# io-board-f-a.net
KiCad netlist of a schematic drawn in EAGLE
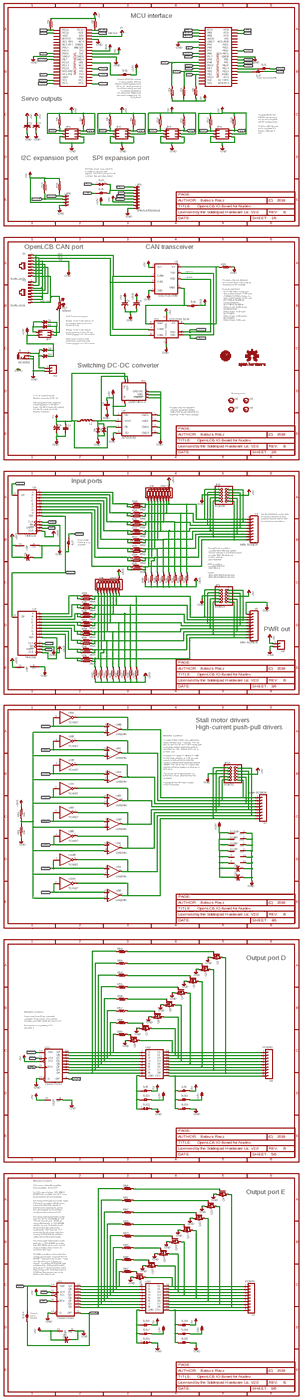
[diagram p0: schematic, sheet 1, overview]
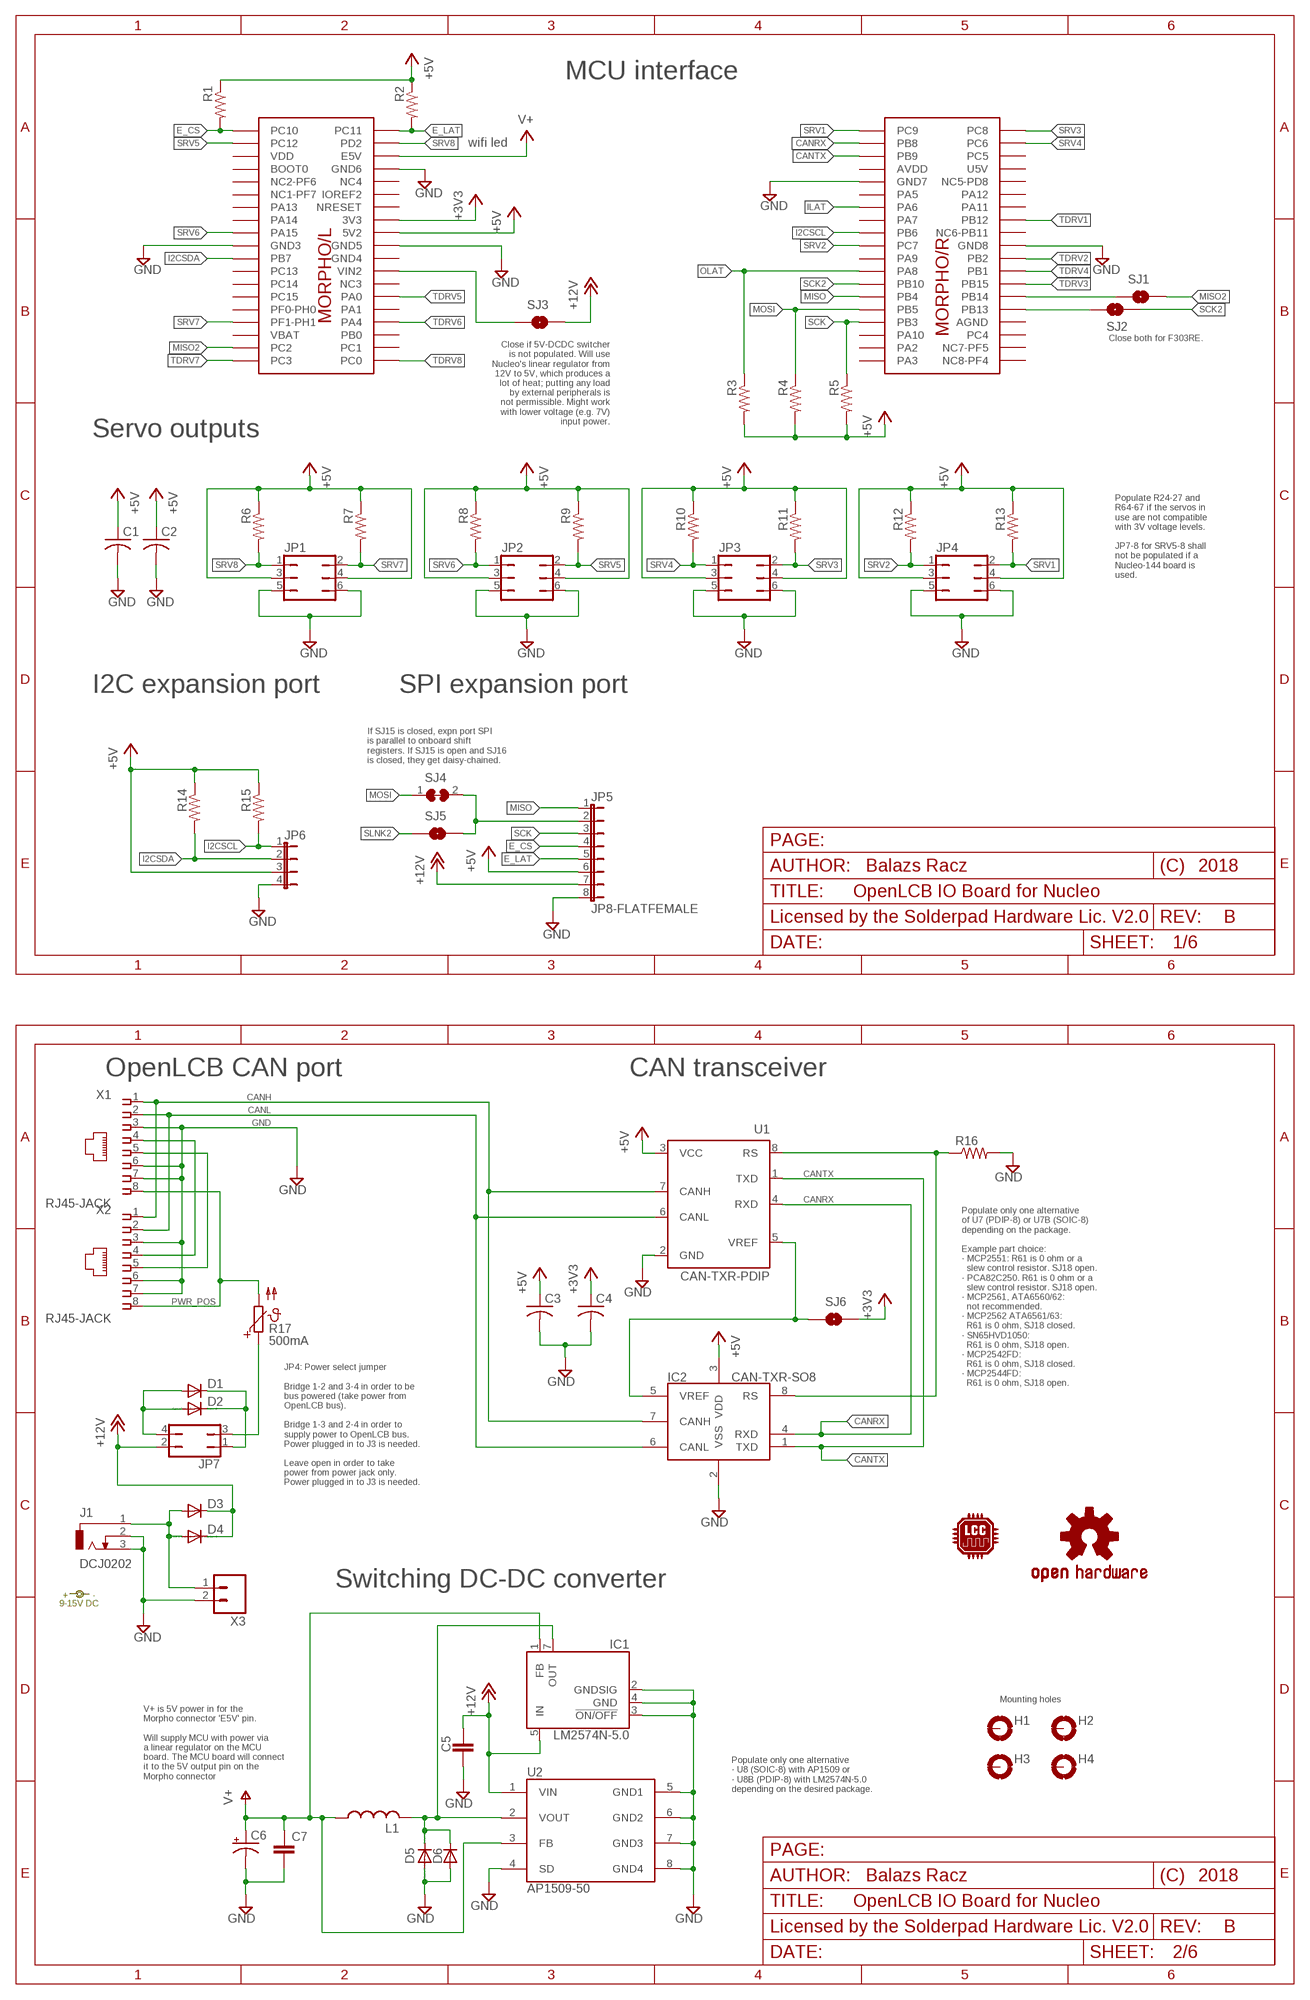
[diagram p1: schematic, sheet 1, part 1 of 4]
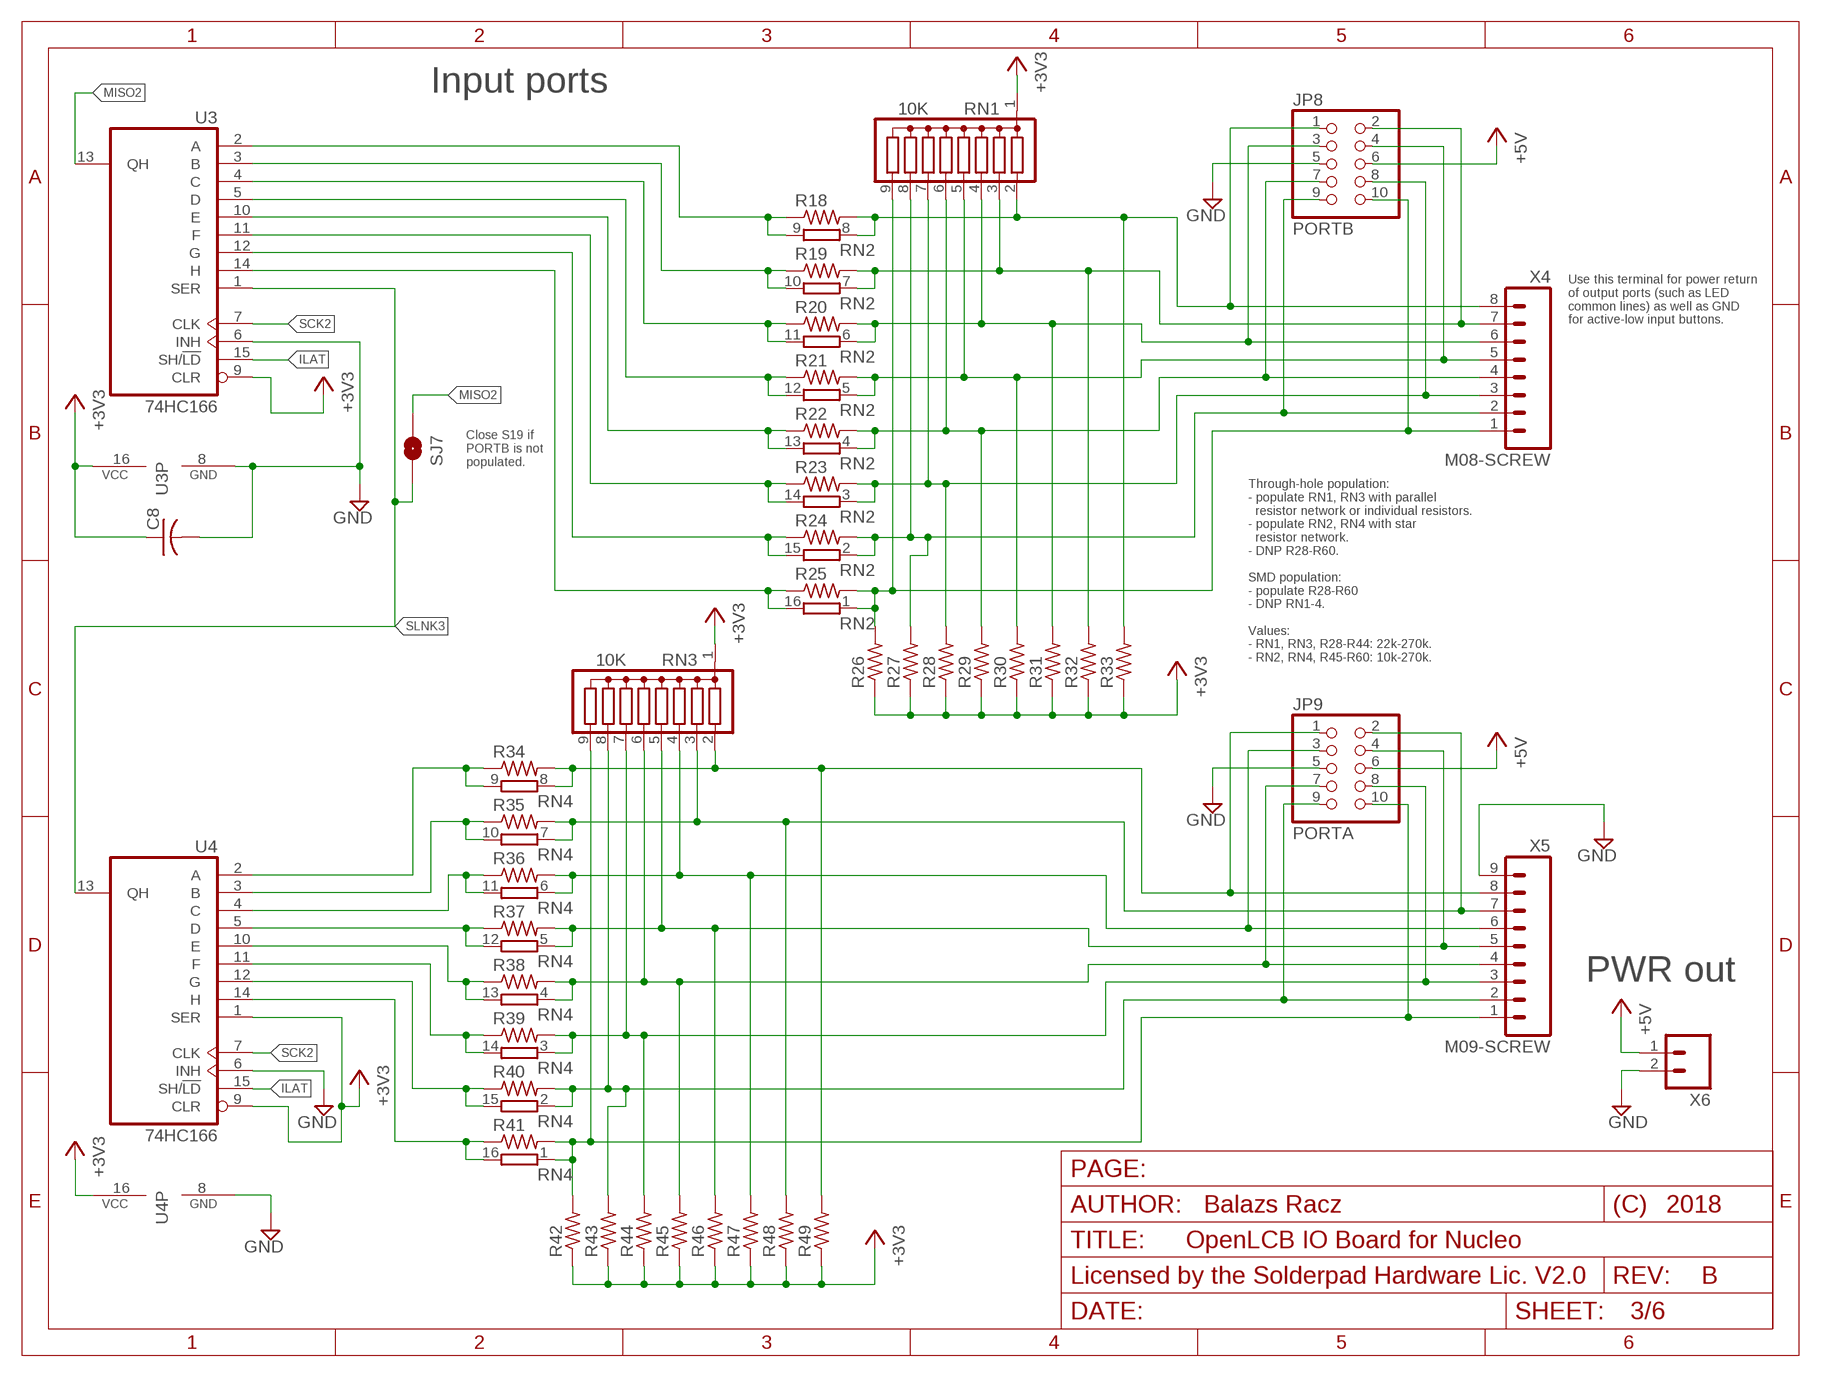
[diagram p2: schematic, sheet 1, part 2 of 4]
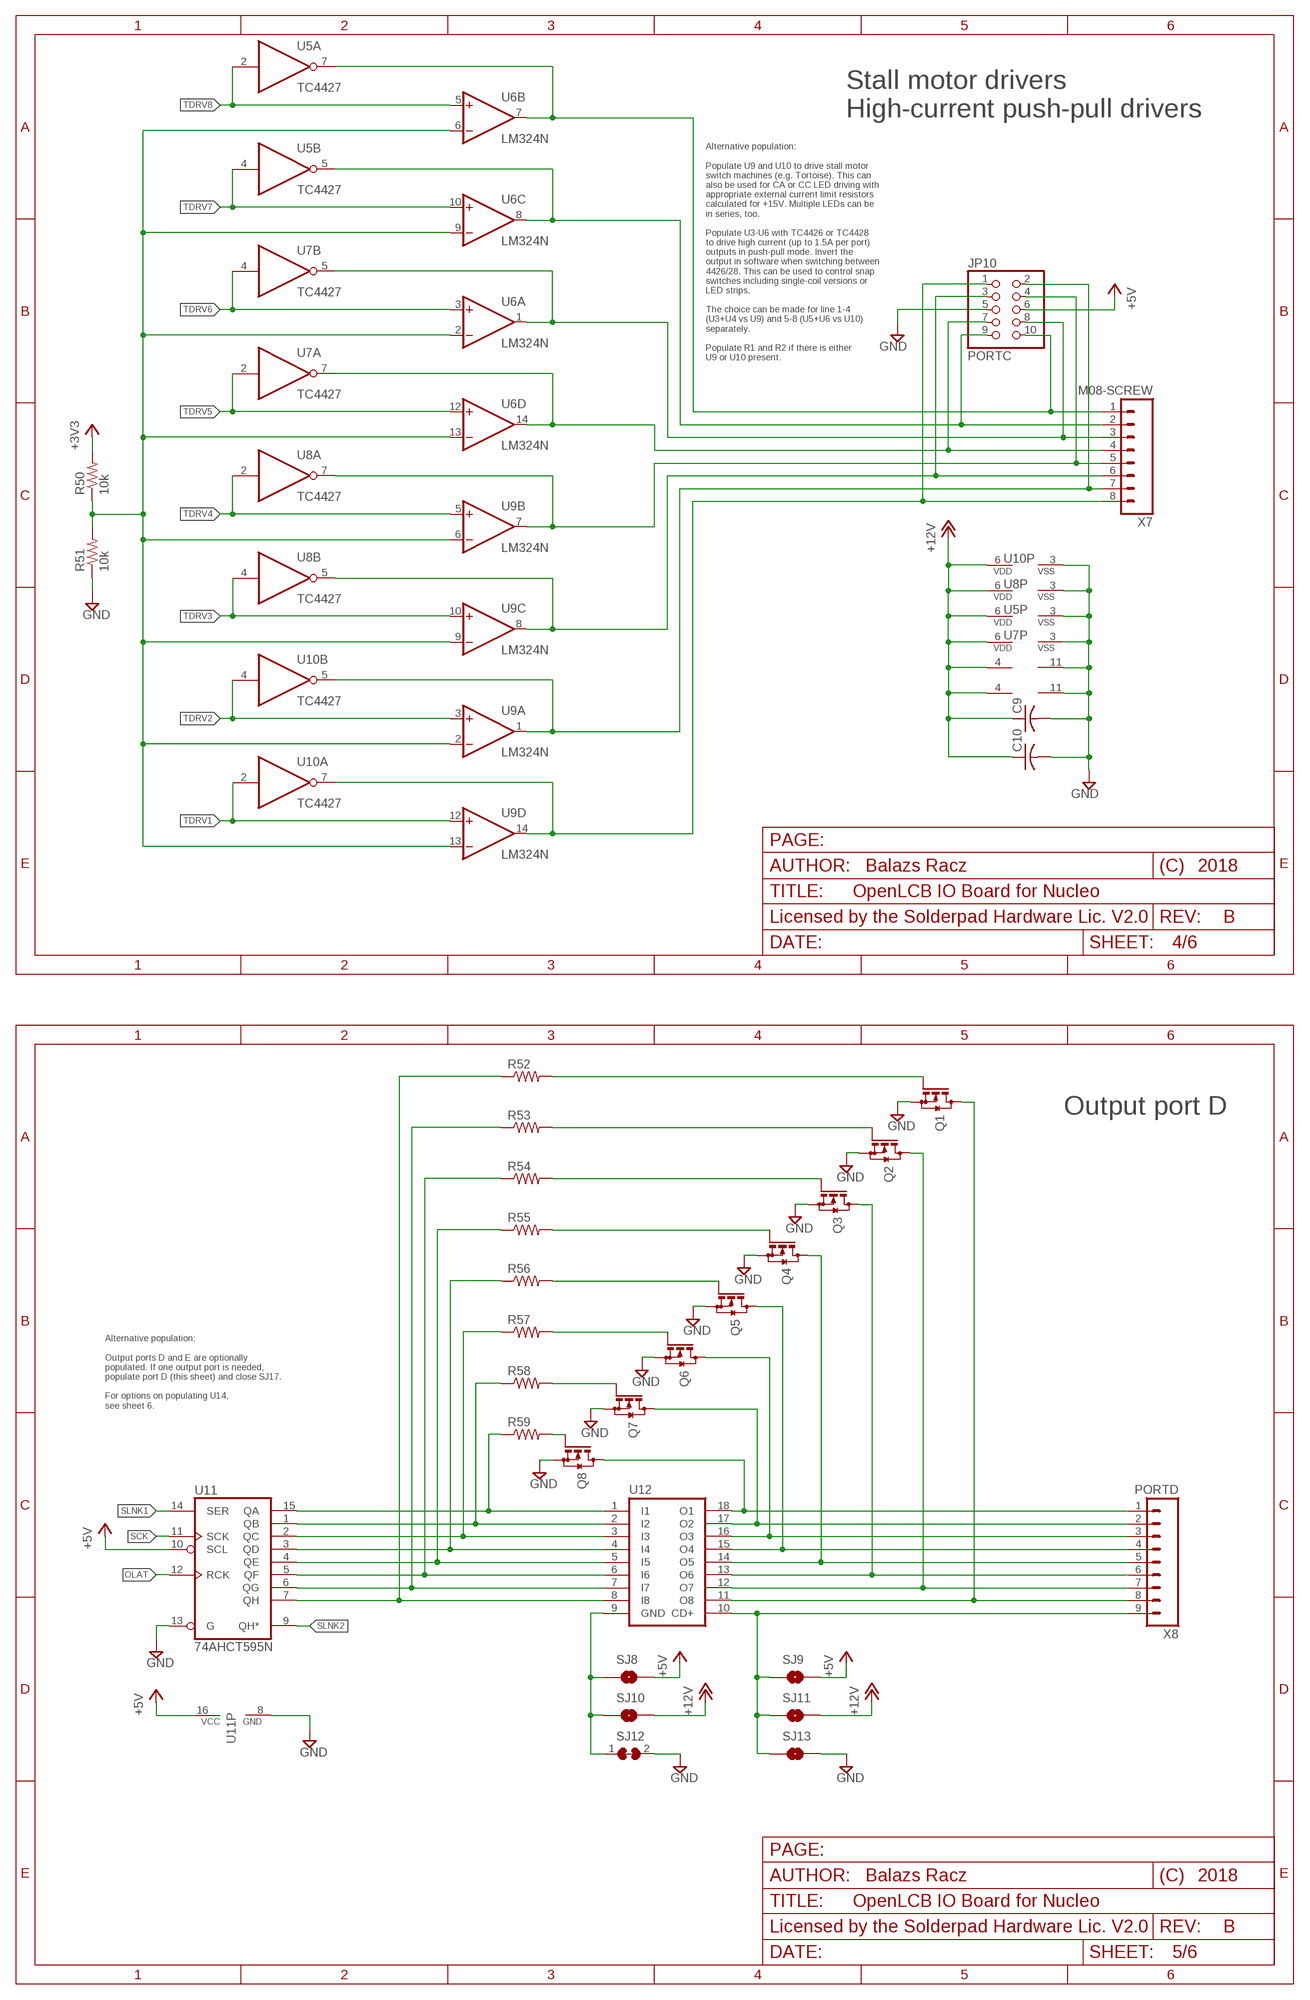
[diagram p3: schematic, sheet 1, part 3 of 4]
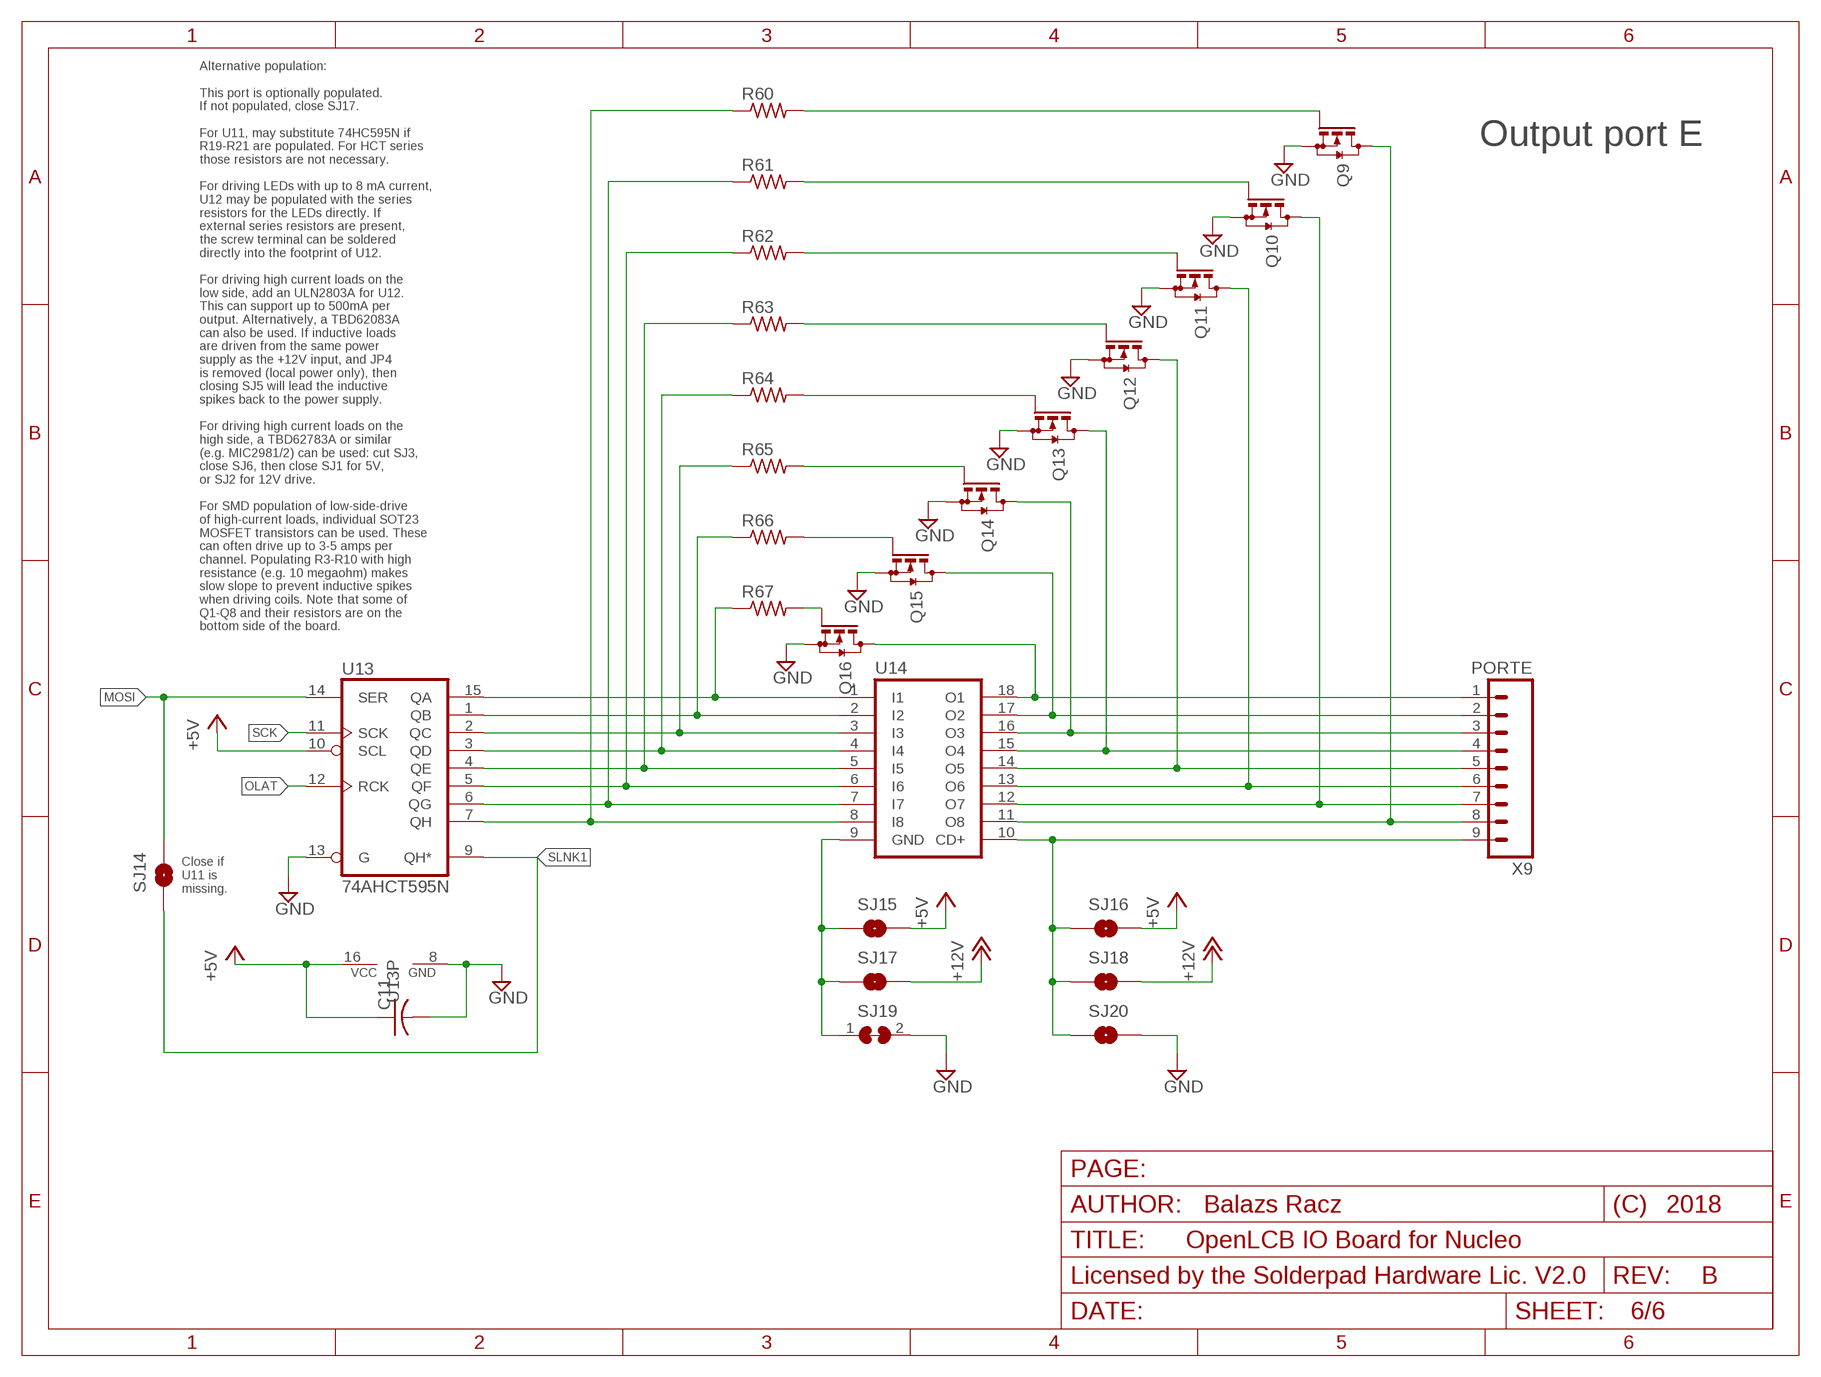
[diagram p4: schematic, sheet 1, part 4 of 4]

(export (version "E")
  (design (tool "Eeschema 10.0.6"))
  (components
    (comp (ref "C1")
      (value "C-USC1206")
      (footprint "eagle-import:C1206")
      (libsource (lib "eagle-import") (part "C-USC1206"))
    )
    (comp (ref "C2")
      (value "C-USC1206")
      (footprint "eagle-import:C1206")
      (libsource (lib "eagle-import") (part "C-USC1206"))
    )
    (comp (ref "C3")
      (value "C-USC0805")
      (footprint "eagle-import:C0805")
      (libsource (lib "eagle-import") (part "C-USC0805"))
    )
    (comp (ref "C4")
      (value "C-USC0805")
      (footprint "eagle-import:C0805")
      (libsource (lib "eagle-import") (part "C-USC0805"))
    )
    (comp (ref "C5")
      (value "C-EUC1206")
      (footprint "eagle-import:C1206")
      (libsource (lib "eagle-import") (part "C-EUC1206"))
    )
    (comp (ref "C6")
      (value "CPOL-USE2.5-5")
      (footprint "eagle-import:E2,5-5")
      (libsource (lib "eagle-import") (part "CPOL-USE2.5-5"))
    )
    (comp (ref "C7")
      (value "C-EUC1206")
      (footprint "eagle-import:C1206")
      (libsource (lib "eagle-import") (part "C-EUC1206"))
    )
    (comp (ref "C8")
      (value "C-USC0805")
      (footprint "eagle-import:C0805")
      (libsource (lib "eagle-import") (part "C-USC0805"))
    )
    (comp (ref "C9")
      (value "C-USC1206")
      (footprint "eagle-import:C1206")
      (libsource (lib "eagle-import") (part "C-USC1206"))
    )
    (comp (ref "C10")
      (value "C-USC1206")
      (footprint "eagle-import:C1206")
      (libsource (lib "eagle-import") (part "C-USC1206"))
    )
    (comp (ref "C11")
      (value "C-USC0805")
      (footprint "eagle-import:C0805")
      (libsource (lib "eagle-import") (part "C-USC0805"))
    )
    (comp (ref "D1")
      (value "DIODEDO-214AA-NODOC")
      (footprint "eagle-import:DO214AA-NODOC")
      (libsource (lib "eagle-import") (part "DIODEDO-214AA-NODOC"))
    )
    (comp (ref "D2")
      (value "DIODE-DO41-7.6")
      (footprint "eagle-import:DO41-7.6")
      (libsource (lib "eagle-import") (part "DIODE-DO41-7.6"))
    )
    (comp (ref "D3")
      (value "DIODEDO-214AA-NODOC")
      (footprint "eagle-import:DO214AA-NODOC")
      (libsource (lib "eagle-import") (part "DIODEDO-214AA-NODOC"))
    )
    (comp (ref "D4")
      (value "DIODE-DO41-7.6")
      (footprint "eagle-import:DO41-7.6")
      (libsource (lib "eagle-import") (part "DIODE-DO41-7.6"))
    )
    (comp (ref "D5")
      (value "DIODE-DO41-7.6")
      (footprint "eagle-import:DO41-7.6")
      (libsource (lib "eagle-import") (part "DIODE-DO41-7.6"))
    )
    (comp (ref "D6")
      (value "DIODEDO-214AA-NODOC")
      (footprint "eagle-import:DO214AA-NODOC")
      (libsource (lib "eagle-import") (part "DIODEDO-214AA-NODOC"))
    )
    (comp (ref "G1")
      (value "NUCLEO_64_GENERIC")
      (footprint "eagle-import:NUCLEO_BRD_BASE64")
      (libsource (lib "eagle-import") (part "NUCLEO_64_GENERIC"))
    )
    (comp (ref "H1")
      (value "MOUNT-PAD-ROUND3.3")
      (footprint "eagle-import:3,3-PAD")
      (libsource (lib "eagle-import") (part "MOUNT-PAD-ROUND3.3"))
    )
    (comp (ref "H2")
      (value "MOUNT-PAD-ROUND3.3")
      (footprint "eagle-import:3,3-PAD")
      (libsource (lib "eagle-import") (part "MOUNT-PAD-ROUND3.3"))
    )
    (comp (ref "H3")
      (value "MOUNT-PAD-ROUND3.3")
      (footprint "eagle-import:3,3-PAD")
      (libsource (lib "eagle-import") (part "MOUNT-PAD-ROUND3.3"))
    )
    (comp (ref "H4")
      (value "MOUNT-PAD-ROUND3.3")
      (footprint "eagle-import:3,3-PAD")
      (libsource (lib "eagle-import") (part "MOUNT-PAD-ROUND3.3"))
    )
    (comp (ref "IC1")
      (value "LM2574N-5.0")
      (footprint "eagle-import:DIL08")
      (libsource (lib "eagle-import") (part "LM2574?-N5.0"))
    )
    (comp (ref "IC2")
      (value "CAN-TXR-SO8")
      (footprint "eagle-import:SO-08")
      (libsource (lib "eagle-import") (part "MCP2551-SN"))
    )
    (comp (ref "J1")
      (value "DCJ0202")
      (footprint "eagle-import:DCJ0202")
      (libsource (lib "eagle-import") (part "DCJ0202"))
    )
    (comp (ref "JP1")
      (value "JP3Q")
      (footprint "eagle-import:JP3Q")
      (libsource (lib "eagle-import") (part "JP3Q"))
    )
    (comp (ref "JP2")
      (value "JP3Q")
      (footprint "eagle-import:JP3Q")
      (libsource (lib "eagle-import") (part "JP3Q"))
    )
    (comp (ref "JP3")
      (value "JP3Q")
      (footprint "eagle-import:JP3Q")
      (libsource (lib "eagle-import") (part "JP3Q"))
    )
    (comp (ref "JP4")
      (value "JP3Q")
      (footprint "eagle-import:JP3Q")
      (libsource (lib "eagle-import") (part "JP3Q"))
    )
    (comp (ref "JP5")
      (value "JP8-FLATFEMALE")
      (footprint "eagle-import:JP8F-FEM")
      (libsource (lib "eagle-import") (part "JP8-FLATFEMALE"))
    )
    (comp (ref "JP6")
      (value "JP4-FLAT")
      (footprint "eagle-import:JP4F")
      (libsource (lib "eagle-import") (part "JP4-FLAT"))
    )
    (comp (ref "JP7")
      (value "JP2Q")
      (footprint "eagle-import:JP2Q")
      (libsource (lib "eagle-import") (part "JP2Q"))
    )
    (comp (ref "JP8")
      (value "PORTB")
      (footprint "eagle-import:CON10M")
      (libsource (lib "eagle-import") (part "PINHD-2X5CN"))
    )
    (comp (ref "JP9")
      (value "PORTA")
      (footprint "eagle-import:CON10M")
      (libsource (lib "eagle-import") (part "PINHD-2X5CN"))
    )
    (comp (ref "JP10")
      (value "PORTC")
      (footprint "eagle-import:CON10M")
      (libsource (lib "eagle-import") (part "PINHD-2X5CN"))
    )
    (comp (ref "L1")
      (value "L-US")
      (footprint "eagle-import:L5-8,5")
      (libsource (lib "eagle-import") (part "L-US"))
    )
    (comp (ref "LG1")
      (value "LCC_LOGO")
      (footprint "eagle-import:LCC_LOGO")
      (libsource (lib "eagle-import") (part "LCC_LOGO"))
    )
    (comp (ref "LOGO1")
      (value "DOC-OSHW-LOGOM")
      (footprint "eagle-import:OSHW-LOGO-M")
      (libsource (lib "eagle-import") (part "DOC-OSHW-LOGOM"))
    )
    (comp (ref "P1")
      (value "9-15V DC")
      (footprint "eagle-import:POWER_USAGE")
      (libsource (lib "eagle-import") (part "DOC-POWER_LABEL"))
    )
    (comp (ref "Q1")
      (value "BSS123")
      (footprint "eagle-import:SOT23")
      (libsource (lib "eagle-import") (part "BSS123"))
    )
    (comp (ref "Q2")
      (value "BSS123")
      (footprint "eagle-import:SOT23")
      (libsource (lib "eagle-import") (part "BSS123"))
    )
    (comp (ref "Q3")
      (value "BSS123")
      (footprint "eagle-import:SOT23")
      (libsource (lib "eagle-import") (part "BSS123"))
    )
    (comp (ref "Q4")
      (value "BSS123")
      (footprint "eagle-import:SOT23")
      (libsource (lib "eagle-import") (part "BSS123"))
    )
    (comp (ref "Q5")
      (value "BSS123")
      (footprint "eagle-import:SOT23")
      (libsource (lib "eagle-import") (part "BSS123"))
    )
    (comp (ref "Q6")
      (value "BSS123")
      (footprint "eagle-import:SOT23")
      (libsource (lib "eagle-import") (part "BSS123"))
    )
    (comp (ref "Q7")
      (value "BSS123")
      (footprint "eagle-import:SOT23")
      (libsource (lib "eagle-import") (part "BSS123"))
    )
    (comp (ref "Q8")
      (value "BSS123")
      (footprint "eagle-import:SOT23")
      (libsource (lib "eagle-import") (part "BSS123"))
    )
    (comp (ref "Q9")
      (value "BSS123")
      (footprint "eagle-import:SOT23")
      (libsource (lib "eagle-import") (part "BSS123"))
    )
    (comp (ref "Q10")
      (value "BSS123")
      (footprint "eagle-import:SOT23")
      (libsource (lib "eagle-import") (part "BSS123"))
    )
    (comp (ref "Q11")
      (value "BSS123")
      (footprint "eagle-import:SOT23")
      (libsource (lib "eagle-import") (part "BSS123"))
    )
    (comp (ref "Q12")
      (value "BSS123")
      (footprint "eagle-import:SOT23")
      (libsource (lib "eagle-import") (part "BSS123"))
    )
    (comp (ref "Q13")
      (value "BSS123")
      (footprint "eagle-import:SOT23")
      (libsource (lib "eagle-import") (part "BSS123"))
    )
    (comp (ref "Q14")
      (value "BSS123")
      (footprint "eagle-import:SOT23")
      (libsource (lib "eagle-import") (part "BSS123"))
    )
    (comp (ref "Q15")
      (value "BSS123")
      (footprint "eagle-import:SOT23")
      (libsource (lib "eagle-import") (part "BSS123"))
    )
    (comp (ref "Q16")
      (value "BSS123")
      (footprint "eagle-import:SOT23")
      (libsource (lib "eagle-import") (part "BSS123"))
    )
    (comp (ref "R1")
      (value "R-US_R0805")
      (footprint "eagle-import:R0805")
      (libsource (lib "eagle-import") (part "rcl_334_R-US_R0805"))
    )
    (comp (ref "R2")
      (value "R-US_R0805")
      (footprint "eagle-import:R0805")
      (libsource (lib "eagle-import") (part "rcl_334_R-US_R0805"))
    )
    (comp (ref "R3")
      (value "R-US_R0805")
      (footprint "eagle-import:R0805")
      (libsource (lib "eagle-import") (part "rcl_334_R-US_R0805"))
    )
    (comp (ref "R4")
      (value "R-US_R0805")
      (footprint "eagle-import:R0805")
      (libsource (lib "eagle-import") (part "rcl_334_R-US_R0805"))
    )
    (comp (ref "R5")
      (value "R-US_R0805")
      (footprint "eagle-import:R0805")
      (libsource (lib "eagle-import") (part "rcl_334_R-US_R0805"))
    )
    (comp (ref "R6")
      (value "R-US_R0805")
      (footprint "eagle-import:R0805")
      (libsource (lib "eagle-import") (part "rcl_334_R-US_R0805"))
    )
    (comp (ref "R7")
      (value "R-US_R0805")
      (footprint "eagle-import:R0805")
      (libsource (lib "eagle-import") (part "rcl_334_R-US_R0805"))
    )
    (comp (ref "R8")
      (value "R-US_R0805")
      (footprint "eagle-import:R0805")
      (libsource (lib "eagle-import") (part "rcl_334_R-US_R0805"))
    )
    (comp (ref "R9")
      (value "R-US_R0805")
      (footprint "eagle-import:R0805")
      (libsource (lib "eagle-import") (part "rcl_334_R-US_R0805"))
    )
    (comp (ref "R10")
      (value "R-US_R0805")
      (footprint "eagle-import:R0805")
      (libsource (lib "eagle-import") (part "rcl_334_R-US_R0805"))
    )
    (comp (ref "R11")
      (value "R-US_R0805")
      (footprint "eagle-import:R0805")
      (libsource (lib "eagle-import") (part "rcl_334_R-US_R0805"))
    )
    (comp (ref "R12")
      (value "R-US_R0805")
      (footprint "eagle-import:R0805")
      (libsource (lib "eagle-import") (part "rcl_334_R-US_R0805"))
    )
    (comp (ref "R13")
      (value "R-US_R0805")
      (footprint "eagle-import:R0805")
      (libsource (lib "eagle-import") (part "rcl_334_R-US_R0805"))
    )
    (comp (ref "R14")
      (value "R-US_R0805")
      (footprint "eagle-import:R0805")
      (libsource (lib "eagle-import") (part "rcl_334_R-US_R0805"))
    )
    (comp (ref "R15")
      (value "R-US_R0805")
      (footprint "eagle-import:R0805")
      (libsource (lib "eagle-import") (part "rcl_334_R-US_R0805"))
    )
    (comp (ref "R16")
      (value "R-US_R0805")
      (footprint "eagle-import:R0805")
      (libsource (lib "eagle-import") (part "rcl_334_R-US_R0805"))
    )
    (comp (ref "R17")
      (value "500mA")
      (footprint "eagle-import:PTC1812")
      (libsource (lib "eagle-import") (part "PTC_1812"))
    )
    (comp (ref "R18")
      (value "R-US_R0603")
      (footprint "eagle-import:R0603")
      (libsource (lib "eagle-import") (part "rcl_334_R-US_R0603"))
    )
    (comp (ref "R19")
      (value "R-US_R0603")
      (footprint "eagle-import:R0603")
      (libsource (lib "eagle-import") (part "rcl_334_R-US_R0603"))
    )
    (comp (ref "R20")
      (value "R-US_R0603")
      (footprint "eagle-import:R0603")
      (libsource (lib "eagle-import") (part "rcl_334_R-US_R0603"))
    )
    (comp (ref "R21")
      (value "R-US_R0603")
      (footprint "eagle-import:R0603")
      (libsource (lib "eagle-import") (part "rcl_334_R-US_R0603"))
    )
    (comp (ref "R22")
      (value "R-US_R0603")
      (footprint "eagle-import:R0603")
      (libsource (lib "eagle-import") (part "rcl_334_R-US_R0603"))
    )
    (comp (ref "R23")
      (value "R-US_R0603")
      (footprint "eagle-import:R0603")
      (libsource (lib "eagle-import") (part "rcl_334_R-US_R0603"))
    )
    (comp (ref "R24")
      (value "R-US_R0603")
      (footprint "eagle-import:R0603")
      (libsource (lib "eagle-import") (part "rcl_334_R-US_R0603"))
    )
    (comp (ref "R25")
      (value "R-US_R0603")
      (footprint "eagle-import:R0603")
      (libsource (lib "eagle-import") (part "rcl_334_R-US_R0603"))
    )
    (comp (ref "R26")
      (value "R-US")
      (footprint "eagle-import:R0603")
      (libsource (lib "eagle-import") (part "R-US"))
    )
    (comp (ref "R27")
      (value "R-US")
      (footprint "eagle-import:R0603")
      (libsource (lib "eagle-import") (part "R-US"))
    )
    (comp (ref "R28")
      (value "R-US")
      (footprint "eagle-import:R0603")
      (libsource (lib "eagle-import") (part "R-US"))
    )
    (comp (ref "R29")
      (value "R-US")
      (footprint "eagle-import:R0603")
      (libsource (lib "eagle-import") (part "R-US"))
    )
    (comp (ref "R30")
      (value "R-US")
      (footprint "eagle-import:R0603")
      (libsource (lib "eagle-import") (part "R-US"))
    )
    (comp (ref "R31")
      (value "R-US")
      (footprint "eagle-import:R0603")
      (libsource (lib "eagle-import") (part "R-US"))
    )
    (comp (ref "R32")
      (value "R-US")
      (footprint "eagle-import:R0603")
      (libsource (lib "eagle-import") (part "R-US"))
    )
    (comp (ref "R33")
      (value "R-US")
      (footprint "eagle-import:R0603")
      (libsource (lib "eagle-import") (part "R-US"))
    )
    (comp (ref "R34")
      (value "R-US_R0603")
      (footprint "eagle-import:R0603")
      (libsource (lib "eagle-import") (part "rcl_334_R-US_R0603"))
    )
    (comp (ref "R35")
      (value "R-US_R0603")
      (footprint "eagle-import:R0603")
      (libsource (lib "eagle-import") (part "rcl_334_R-US_R0603"))
    )
    (comp (ref "R36")
      (value "R-US_R0603")
      (footprint "eagle-import:R0603")
      (libsource (lib "eagle-import") (part "rcl_334_R-US_R0603"))
    )
    (comp (ref "R37")
      (value "R-US_R0603")
      (footprint "eagle-import:R0603")
      (libsource (lib "eagle-import") (part "rcl_334_R-US_R0603"))
    )
    (comp (ref "R38")
      (value "R-US_R0603")
      (footprint "eagle-import:R0603")
      (libsource (lib "eagle-import") (part "rcl_334_R-US_R0603"))
    )
    (comp (ref "R39")
      (value "R-US_R0603")
      (footprint "eagle-import:R0603")
      (libsource (lib "eagle-import") (part "rcl_334_R-US_R0603"))
    )
    (comp (ref "R40")
      (value "R-US_R0603")
      (footprint "eagle-import:R0603")
      (libsource (lib "eagle-import") (part "rcl_334_R-US_R0603"))
    )
    (comp (ref "R41")
      (value "R-US_R0603")
      (footprint "eagle-import:R0603")
      (libsource (lib "eagle-import") (part "rcl_334_R-US_R0603"))
    )
    (comp (ref "R42")
      (value "R-US")
      (footprint "eagle-import:R0603")
      (libsource (lib "eagle-import") (part "R-US"))
    )
    (comp (ref "R43")
      (value "R-US")
      (footprint "eagle-import:R0603")
      (libsource (lib "eagle-import") (part "R-US"))
    )
    (comp (ref "R44")
      (value "R-US")
      (footprint "eagle-import:R0603")
      (libsource (lib "eagle-import") (part "R-US"))
    )
    (comp (ref "R45")
      (value "R-US")
      (footprint "eagle-import:R0603")
      (libsource (lib "eagle-import") (part "R-US"))
    )
    (comp (ref "R46")
      (value "R-US")
      (footprint "eagle-import:R0603")
      (libsource (lib "eagle-import") (part "R-US"))
    )
    (comp (ref "R47")
      (value "R-US")
      (footprint "eagle-import:R0603")
      (libsource (lib "eagle-import") (part "R-US"))
    )
    (comp (ref "R48")
      (value "R-US")
      (footprint "eagle-import:R0603")
      (libsource (lib "eagle-import") (part "R-US"))
    )
    (comp (ref "R49")
      (value "R-US")
      (footprint "eagle-import:R0603")
      (libsource (lib "eagle-import") (part "R-US"))
    )
    (comp (ref "R50")
      (value "10k")
      (footprint "eagle-import:R0805")
      (libsource (lib "eagle-import") (part "R-US_R0805"))
    )
    (comp (ref "R51")
      (value "10k")
      (footprint "eagle-import:R0805")
      (libsource (lib "eagle-import") (part "R-US_R0805"))
    )
    (comp (ref "R52")
      (value "R-US_R0603")
      (footprint "eagle-import:R0603")
      (libsource (lib "eagle-import") (part "R-US_R0603"))
    )
    (comp (ref "R53")
      (value "R-US_R0603")
      (footprint "eagle-import:R0603")
      (libsource (lib "eagle-import") (part "R-US_R0603"))
    )
    (comp (ref "R54")
      (value "R-US_R0603")
      (footprint "eagle-import:R0603")
      (libsource (lib "eagle-import") (part "R-US_R0603"))
    )
    (comp (ref "R55")
      (value "R-US_R0603")
      (footprint "eagle-import:R0603")
      (libsource (lib "eagle-import") (part "R-US_R0603"))
    )
    (comp (ref "R56")
      (value "R-US_R0603")
      (footprint "eagle-import:R0603")
      (libsource (lib "eagle-import") (part "R-US_R0603"))
    )
    (comp (ref "R57")
      (value "R-US_R0603")
      (footprint "eagle-import:R0603")
      (libsource (lib "eagle-import") (part "R-US_R0603"))
    )
    (comp (ref "R58")
      (value "R-US_R0603")
      (footprint "eagle-import:R0603")
      (libsource (lib "eagle-import") (part "R-US_R0603"))
    )
    (comp (ref "R59")
      (value "R-US_R0603")
      (footprint "eagle-import:R0603")
      (libsource (lib "eagle-import") (part "R-US_R0603"))
    )
    (comp (ref "R60")
      (value "R-US_R0603")
      (footprint "eagle-import:R0603")
      (libsource (lib "eagle-import") (part "R-US_R0603"))
    )
    (comp (ref "R61")
      (value "R-US_R0603")
      (footprint "eagle-import:R0603")
      (libsource (lib "eagle-import") (part "R-US_R0603"))
    )
    (comp (ref "R62")
      (value "R-US_R0603")
      (footprint "eagle-import:R0603")
      (libsource (lib "eagle-import") (part "R-US_R0603"))
    )
    (comp (ref "R63")
      (value "R-US_R0603")
      (footprint "eagle-import:R0603")
      (libsource (lib "eagle-import") (part "R-US_R0603"))
    )
    (comp (ref "R64")
      (value "R-US_R0603")
      (footprint "eagle-import:R0603")
      (libsource (lib "eagle-import") (part "R-US_R0603"))
    )
    (comp (ref "R65")
      (value "R-US_R0603")
      (footprint "eagle-import:R0603")
      (libsource (lib "eagle-import") (part "R-US_R0603"))
    )
    (comp (ref "R66")
      (value "R-US_R0603")
      (footprint "eagle-import:R0603")
      (libsource (lib "eagle-import") (part "R-US_R0603"))
    )
    (comp (ref "R67")
      (value "R-US_R0603")
      (footprint "eagle-import:R0603")
      (libsource (lib "eagle-import") (part "R-US_R0603"))
    )
    (comp (ref "RN1")
      (value "10K")
      (footprint "eagle-import:SIL9")
      (libsource (lib "eagle-import") (part "G08R"))
    )
    (comp (ref "RN2")
      (value "8R-P")
      (footprint "eagle-import:DIL16")
      (libsource (lib "eagle-import") (part "8R-P"))
    )
    (comp (ref "RN3")
      (value "10K")
      (footprint "eagle-import:SIL9")
      (libsource (lib "eagle-import") (part "G08R"))
    )
    (comp (ref "RN4")
      (value "8R-P")
      (footprint "eagle-import:DIL16")
      (libsource (lib "eagle-import") (part "8R-P"))
    )
    (comp (ref "SJ1")
      (value "SJRND2")
      (footprint "eagle-import:SJ_RND2")
      (libsource (lib "eagle-import") (part "SJRND2"))
    )
    (comp (ref "SJ2")
      (value "SJRND2")
      (footprint "eagle-import:SJ_RND2")
      (libsource (lib "eagle-import") (part "SJRND2"))
    )
    (comp (ref "SJ3")
      (value "SJRND2")
      (footprint "eagle-import:SJ_RND2")
      (libsource (lib "eagle-import") (part "SJRND2"))
    )
    (comp (ref "SJ4")
      (value "SJ-C")
      (footprint "eagle-import:SJW-C")
      (libsource (lib "eagle-import") (part "SJ-C"))
    )
    (comp (ref "SJ5")
      (value "SJRND2")
      (footprint "eagle-import:SJ_RND2")
      (libsource (lib "eagle-import") (part "SJRND2"))
    )
    (comp (ref "SJ6")
      (value "SJRND2")
      (footprint "eagle-import:SJ_RND2")
      (libsource (lib "eagle-import") (part "SJRND2"))
    )
    (comp (ref "SJ7")
      (value "SJRND2")
      (footprint "eagle-import:SJ_RND2")
      (libsource (lib "eagle-import") (part "SJRND2"))
    )
    (comp (ref "SJ8")
      (value "SJRND2")
      (footprint "eagle-import:SJ_RND2")
      (libsource (lib "eagle-import") (part "SJRND2"))
    )
    (comp (ref "SJ9")
      (value "SJRND2")
      (footprint "eagle-import:SJ_RND2")
      (libsource (lib "eagle-import") (part "SJRND2"))
    )
    (comp (ref "SJ10")
      (value "SJRND2")
      (footprint "eagle-import:SJ_RND2")
      (libsource (lib "eagle-import") (part "SJRND2"))
    )
    (comp (ref "SJ11")
      (value "SJRND2")
      (footprint "eagle-import:SJ_RND2")
      (libsource (lib "eagle-import") (part "SJRND2"))
    )
    (comp (ref "SJ12")
      (value "SJ-C")
      (footprint "eagle-import:SJW-C")
      (libsource (lib "eagle-import") (part "SJ-C"))
    )
    (comp (ref "SJ13")
      (value "SJRND2")
      (footprint "eagle-import:SJ_RND2")
      (libsource (lib "eagle-import") (part "SJRND2"))
    )
    (comp (ref "SJ14")
      (value "SJRND2")
      (footprint "eagle-import:SJ_RND2")
      (libsource (lib "eagle-import") (part "SJRND2"))
    )
    (comp (ref "SJ15")
      (value "SJRND2")
      (footprint "eagle-import:SJ_RND2")
      (libsource (lib "eagle-import") (part "SJRND2"))
    )
    (comp (ref "SJ16")
      (value "SJRND2")
      (footprint "eagle-import:SJ_RND2")
      (libsource (lib "eagle-import") (part "SJRND2"))
    )
    (comp (ref "SJ17")
      (value "SJRND2")
      (footprint "eagle-import:SJ_RND2")
      (libsource (lib "eagle-import") (part "SJRND2"))
    )
    (comp (ref "SJ18")
      (value "SJRND2")
      (footprint "eagle-import:SJ_RND2")
      (libsource (lib "eagle-import") (part "SJRND2"))
    )
    (comp (ref "SJ19")
      (value "SJ-C")
      (footprint "eagle-import:SJW-C")
      (libsource (lib "eagle-import") (part "SJ-C"))
    )
    (comp (ref "SJ20")
      (value "SJRND2")
      (footprint "eagle-import:SJ_RND2")
      (libsource (lib "eagle-import") (part "SJRND2"))
    )
    (comp (ref "U1")
      (value "CAN-TXR-PDIP")
      (footprint "eagle-import:DIL08")
      (libsource (lib "eagle-import") (part "PCA82C250"))
    )
    (comp (ref "U2")
      (value "AP1509-50")
      (footprint "eagle-import:SO-08")
      (libsource (lib "eagle-import") (part "AP1509"))
    )
    (comp (ref "U3")
      (value "74HC166")
      (footprint "eagle-import:DIL16")
      (libsource (lib "eagle-import") (part "74166N"))
    )
    (comp (ref "U4")
      (value "74HC166")
      (footprint "eagle-import:DIL16")
      (libsource (lib "eagle-import") (part "74166N"))
    )
    (comp (ref "U5")
      (value "TC4427")
      (footprint "eagle-import:DIL08-LONG")
      (libsource (lib "eagle-import") (part "TC4426APDIP"))
    )
    (comp (ref "U6")
      (value "LM324N")
      (footprint "eagle-import:DIL14")
      (libsource (lib "eagle-import") (part "LM324N"))
    )
    (comp (ref "U7")
      (value "TC4427")
      (footprint "eagle-import:DIL08-LONG")
      (libsource (lib "eagle-import") (part "TC4426APDIP"))
    )
    (comp (ref "U8")
      (value "TC4427")
      (footprint "eagle-import:DIL08-LONG")
      (libsource (lib "eagle-import") (part "TC4426APDIP"))
    )
    (comp (ref "U9")
      (value "LM324N")
      (footprint "eagle-import:DIL14")
      (libsource (lib "eagle-import") (part "LM324N"))
    )
    (comp (ref "U10")
      (value "TC4427")
      (footprint "eagle-import:DIL08-LONG")
      (libsource (lib "eagle-import") (part "TC4426APDIP"))
    )
    (comp (ref "U11")
      (value "74AHCT595N")
      (footprint "eagle-import:DIL16")
      (libsource (lib "eagle-import") (part "74595NHCT"))
    )
    (comp (ref "U12")
      (value "ULN2803A")
      (footprint "eagle-import:DIL18-THIN")
      (libsource (lib "eagle-import") (part "ULN2803A"))
    )
    (comp (ref "U13")
      (value "74AHCT595N")
      (footprint "eagle-import:DIL16")
      (libsource (lib "eagle-import") (part "74595NHCT"))
    )
    (comp (ref "U14")
      (value "ULN2803A")
      (footprint "eagle-import:DIL18-THIN")
      (libsource (lib "eagle-import") (part "ULN2803A"))
    )
    (comp (ref "X1")
      (value "RJ45-JACK")
      (footprint "eagle-import:RJ45-PULSE-E5J88")
      (libsource (lib "eagle-import") (part "RJ45-JACKRJ45-PULSE-E5J00"))
    )
    (comp (ref "X2")
      (value "RJ45-JACK")
      (footprint "eagle-import:RJ45-PULSE-E5J88")
      (libsource (lib "eagle-import") (part "RJ45-JACKRJ45-PULSE-E5J00"))
    )
    (comp (ref "X3")
      (value "CONNECTOR-M023.5MM-LOCK")
      (footprint "eagle-import:SCREWTERMINAL-3.5MM-2_LOCK")
      (libsource (lib "eagle-import") (part "CONNECTOR-M023.5MM-LOCK"))
    )
    (comp (ref "X4")
      (value "M08-SCREW")
      (footprint "eagle-import:1X08_TERMINAL")
      (libsource (lib "eagle-import") (part "M08-SCREW"))
    )
    (comp (ref "X5")
      (value "M09-SCREW")
      (footprint "eagle-import:1X09_TERMINAL")
      (libsource (lib "eagle-import") (part "M09-SCREW"))
    )
    (comp (ref "X6")
      (value "CONNECTOR-M023.5MM-LOCK")
      (footprint "eagle-import:SCREWTERMINAL-3.5MM-2_LOCK")
      (libsource (lib "eagle-import") (part "CONNECTOR-M023.5MM-LOCK"))
    )
    (comp (ref "X7")
      (value "M08-SCREW")
      (footprint "eagle-import:1X08_TERMINAL")
      (libsource (lib "eagle-import") (part "M08-SCREW"))
    )
    (comp (ref "X8")
      (value "PORTD")
      (footprint "eagle-import:1X09_TERMINAL")
      (libsource (lib "eagle-import") (part "M09-SCREW"))
    )
    (comp (ref "X9")
      (value "PORTE")
      (footprint "eagle-import:1X09_TERMINAL")
      (libsource (lib "eagle-import") (part "M09-SCREW"))
    )
  )
  (nets
    (net (code "1") (name "+3V3") (class "Default")
      (node (ref "C4") (pin "1") (pinfunction "1_1") (pintype "passive"))
      (node (ref "C8") (pin "1") (pinfunction "1_1") (pintype "passive"))
      (node (ref "G1") (pin "3V3") (pinfunction "3V3_3V3") (pintype "power_in"))
      (node (ref "R26") (pin "1") (pinfunction "1_1") (pintype "passive"))
      (node (ref "R27") (pin "1") (pinfunction "1_1") (pintype "passive"))
      (node (ref "R28") (pin "1") (pinfunction "1_1") (pintype "passive"))
      (node (ref "R29") (pin "1") (pinfunction "1_1") (pintype "passive"))
      (node (ref "R30") (pin "1") (pinfunction "1_1") (pintype "passive"))
      (node (ref "R31") (pin "1") (pinfunction "1_1") (pintype "passive"))
      (node (ref "R32") (pin "1") (pinfunction "1_1") (pintype "passive"))
      (node (ref "R33") (pin "1") (pinfunction "1_1") (pintype "passive"))
      (node (ref "R42") (pin "1") (pinfunction "1_1") (pintype "passive"))
      (node (ref "R43") (pin "1") (pinfunction "1_1") (pintype "passive"))
      (node (ref "R44") (pin "1") (pinfunction "1_1") (pintype "passive"))
      (node (ref "R45") (pin "1") (pinfunction "1_1") (pintype "passive"))
      (node (ref "R46") (pin "1") (pinfunction "1_1") (pintype "passive"))
      (node (ref "R47") (pin "1") (pinfunction "1_1") (pintype "passive"))
      (node (ref "R48") (pin "1") (pinfunction "1_1") (pintype "passive"))
      (node (ref "R49") (pin "1") (pinfunction "1_1") (pintype "passive"))
      (node (ref "R50") (pin "2") (pinfunction "2_2") (pintype "passive"))
      (node (ref "RN1") (pin "1") (pinfunction "1_1") (pintype "passive"))
      (node (ref "RN3") (pin "1") (pinfunction "1_1") (pintype "passive"))
      (node (ref "SJ6") (pin "P$1") (pinfunction "1_P$1") (pintype "passive"))
      (node (ref "U3") (pin "16") (pinfunction "VCC_16") (pintype "power_in"))
      (node (ref "U3") (pin "9") (pinfunction "CLR_9") (pintype "input"))
      (node (ref "U4") (pin "1") (pinfunction "SER_1") (pintype "input"))
      (node (ref "U4") (pin "16") (pinfunction "VCC_16") (pintype "power_in"))
      (node (ref "U4") (pin "9") (pinfunction "CLR_9") (pintype "input"))
    )
    (net (code "2") (name "+5V") (class "Default")
      (node (ref "C1") (pin "1") (pinfunction "1_1") (pintype "passive"))
      (node (ref "C11") (pin "1") (pinfunction "1_1") (pintype "passive"))
      (node (ref "C2") (pin "1") (pinfunction "1_1") (pintype "passive"))
      (node (ref "C3") (pin "1") (pinfunction "1_1") (pintype "passive"))
      (node (ref "G1") (pin "5V2") (pinfunction "5V2_5V2") (pintype "power_in"))
      (node (ref "IC2") (pin "3") (pinfunction "VDD_3") (pintype "power_in"))
      (node (ref "JP1") (pin "3") (pinfunction "3_3") (pintype "passive"))
      (node (ref "JP1") (pin "4") (pinfunction "4_4") (pintype "passive"))
      (node (ref "JP10") (pin "6") (pinfunction "6_6") (pintype "passive"))
      (node (ref "JP2") (pin "3") (pinfunction "3_3") (pintype "passive"))
      (node (ref "JP2") (pin "4") (pinfunction "4_4") (pintype "passive"))
      (node (ref "JP3") (pin "3") (pinfunction "3_3") (pintype "passive"))
      (node (ref "JP3") (pin "4") (pinfunction "4_4") (pintype "passive"))
      (node (ref "JP4") (pin "3") (pinfunction "3_3") (pintype "passive"))
      (node (ref "JP4") (pin "4") (pinfunction "4_4") (pintype "passive"))
      (node (ref "JP5") (pin "6") (pinfunction "6_6") (pintype "passive"))
      (node (ref "JP6") (pin "3") (pinfunction "3_3") (pintype "passive"))
      (node (ref "JP8") (pin "6") (pinfunction "6_6") (pintype "passive"))
      (node (ref "JP9") (pin "6") (pinfunction "6_6") (pintype "passive"))
      (node (ref "R1") (pin "1") (pinfunction "1_1") (pintype "passive"))
      (node (ref "R10") (pin "1") (pinfunction "1_1") (pintype "passive"))
      (node (ref "R11") (pin "1") (pinfunction "1_1") (pintype "passive"))
      (node (ref "R12") (pin "1") (pinfunction "1_1") (pintype "passive"))
      (node (ref "R13") (pin "1") (pinfunction "1_1") (pintype "passive"))
      (node (ref "R14") (pin "1") (pinfunction "1_1") (pintype "passive"))
      (node (ref "R15") (pin "1") (pinfunction "1_1") (pintype "passive"))
      (node (ref "R2") (pin "1") (pinfunction "1_1") (pintype "passive"))
      (node (ref "R3") (pin "2") (pinfunction "2_2") (pintype "passive"))
      (node (ref "R4") (pin "2") (pinfunction "2_2") (pintype "passive"))
      (node (ref "R5") (pin "2") (pinfunction "2_2") (pintype "passive"))
      (node (ref "R6") (pin "1") (pinfunction "1_1") (pintype "passive"))
      (node (ref "R7") (pin "1") (pinfunction "1_1") (pintype "passive"))
      (node (ref "R8") (pin "1") (pinfunction "1_1") (pintype "passive"))
      (node (ref "R9") (pin "1") (pinfunction "1_1") (pintype "passive"))
      (node (ref "SJ15") (pin "P$2") (pinfunction "2_P$2") (pintype "passive"))
      (node (ref "SJ16") (pin "P$2") (pinfunction "2_P$2") (pintype "passive"))
      (node (ref "SJ8") (pin "P$2") (pinfunction "2_P$2") (pintype "passive"))
      (node (ref "SJ9") (pin "P$2") (pinfunction "2_P$2") (pintype "passive"))
      (node (ref "U1") (pin "3") (pinfunction "VCC_3") (pintype "power_in"))
      (node (ref "U11") (pin "10") (pinfunction "SCL_10") (pintype "input"))
      (node (ref "U11") (pin "16") (pinfunction "VCC_16") (pintype "power_in"))
      (node (ref "U13") (pin "10") (pinfunction "SCL_10") (pintype "input"))
      (node (ref "U13") (pin "16") (pinfunction "VCC_16") (pintype "power_in"))
      (node (ref "X6") (pin "1") (pinfunction "1_1") (pintype "passive"))
    )
    (net (code "3") (name "+12V") (class "Default")
      (node (ref "C10") (pin "1") (pinfunction "1_1") (pintype "passive"))
      (node (ref "C5") (pin "1") (pinfunction "1_1") (pintype "passive"))
      (node (ref "C9") (pin "1") (pinfunction "1_1") (pintype "passive"))
      (node (ref "D3") (pin "C") (pinfunction "C_C") (pintype "passive"))
      (node (ref "D4") (pin "C") (pinfunction "C_C") (pintype "passive"))
      (node (ref "IC1") (pin "5") (pinfunction "IN_5") (pintype "input"))
      (node (ref "JP5") (pin "7") (pinfunction "7_7") (pintype "passive"))
      (node (ref "JP7") (pin "2") (pinfunction "2_2") (pintype "passive"))
      (node (ref "SJ10") (pin "P$2") (pinfunction "2_P$2") (pintype "passive"))
      (node (ref "SJ11") (pin "P$2") (pinfunction "2_P$2") (pintype "passive"))
      (node (ref "SJ17") (pin "P$2") (pinfunction "2_P$2") (pintype "passive"))
      (node (ref "SJ18") (pin "P$2") (pinfunction "2_P$2") (pintype "passive"))
      (node (ref "SJ3") (pin "P$2") (pinfunction "2_P$2") (pintype "passive"))
      (node (ref "U10") (pin "6") (pinfunction "VDD_6") (pintype "power_in"))
      (node (ref "U2") (pin "1") (pinfunction "VIN_1") (pintype "bidirectional"))
      (node (ref "U5") (pin "6") (pinfunction "VDD_6") (pintype "power_in"))
      (node (ref "U6") (pin "4") (pinfunction "V+_4") (pintype "power_in"))
      (node (ref "U7") (pin "6") (pinfunction "VDD_6") (pintype "power_in"))
      (node (ref "U8") (pin "6") (pinfunction "VDD_6") (pintype "power_in"))
      (node (ref "U9") (pin "4") (pinfunction "V+_4") (pintype "power_in"))
    )
    (net (code "4") (name "/AGND") (class "Default")
      (node (ref "G1") (pin "AGND") (pinfunction "AGND_AGND") (pintype "power_in"))
    )
    (net (code "5") (name "/AVDD") (class "Default")
      (node (ref "G1") (pin "AVDD") (pinfunction "AVDD_AVDD") (pintype "power_in"))
    )
    (net (code "6") (name "/CANH") (class "Default")
      (node (ref "IC2") (pin "7") (pinfunction "CANH_7") (pintype "bidirectional"))
      (node (ref "U1") (pin "7") (pinfunction "CANH_7") (pintype "bidirectional"))
      (node (ref "X1") (pin "1") (pinfunction "1_1") (pintype "passive"))
      (node (ref "X2") (pin "1") (pinfunction "1_1") (pintype "passive"))
    )
    (net (code "7") (name "/CANL") (class "Default")
      (node (ref "IC2") (pin "6") (pinfunction "CANL_6") (pintype "bidirectional"))
      (node (ref "U1") (pin "6") (pinfunction "CANL_6") (pintype "bidirectional"))
      (node (ref "X1") (pin "2") (pinfunction "2_2") (pintype "passive"))
      (node (ref "X2") (pin "2") (pinfunction "2_2") (pintype "passive"))
    )
    (net (code "8") (name "/GND4") (class "Default")
      (node (ref "G1") (pin "GND4") (pinfunction "GND4_GND4") (pintype "power_in"))
    )
    (net (code "9") (name "/PWR_POS") (class "Default")
      (node (ref "R17") (pin "2") (pinfunction "2_2") (pintype "passive"))
      (node (ref "X1") (pin "8") (pinfunction "8_8") (pintype "passive"))
      (node (ref "X2") (pin "8") (pinfunction "8_8") (pintype "passive"))
    )
    (net (code "10") (name "/U5V") (class "Default")
      (node (ref "G1") (pin "U5V") (pinfunction "U5V_U5V") (pintype "power_in"))
    )
    (net (code "11") (name "/VBAT") (class "Default")
      (node (ref "G1") (pin "VBAT") (pinfunction "VBAT_VBAT") (pintype "power_in"))
    )
    (net (code "12") (name "/VDD") (class "Default")
      (node (ref "G1") (pin "VDD") (pinfunction "VDD_VDD") (pintype "power_in"))
    )
    (net (code "13") (name "CANRX") (class "Default")
      (node (ref "G1") (pin "PB8") (pinfunction "PB8_PB8") (pintype "bidirectional"))
      (node (ref "IC2") (pin "4") (pinfunction "RXD_4") (pintype "bidirectional"))
      (node (ref "U1") (pin "4") (pinfunction "RXD_4") (pintype "output"))
    )
    (net (code "14") (name "CANTX") (class "Default")
      (node (ref "G1") (pin "PB9") (pinfunction "PB9_PB9") (pintype "bidirectional"))
      (node (ref "IC2") (pin "1") (pinfunction "TXD_1") (pintype "bidirectional"))
      (node (ref "U1") (pin "1") (pinfunction "TXD_1") (pintype "input"))
    )
    (net (code "15") (name "E_CS") (class "Default")
      (node (ref "G1") (pin "PC10") (pinfunction "PC10_PC10") (pintype "bidirectional"))
      (node (ref "JP5") (pin "4") (pinfunction "4_4") (pintype "passive"))
      (node (ref "R1") (pin "2") (pinfunction "2_2") (pintype "passive"))
    )
    (net (code "16") (name "E_LAT") (class "Default")
      (node (ref "G1") (pin "PC11") (pinfunction "PC11_PC11") (pintype "bidirectional"))
      (node (ref "JP5") (pin "5") (pinfunction "5_5") (pintype "passive"))
      (node (ref "R2") (pin "2") (pinfunction "2_2") (pintype "passive"))
    )
    (net (code "17") (name "GND") (class "Default")
      (node (ref "C1") (pin "2") (pinfunction "2_2") (pintype "passive"))
      (node (ref "C10") (pin "2") (pinfunction "2_2") (pintype "passive"))
      (node (ref "C11") (pin "2") (pinfunction "2_2") (pintype "passive"))
      (node (ref "C2") (pin "2") (pinfunction "2_2") (pintype "passive"))
      (node (ref "C3") (pin "2") (pinfunction "2_2") (pintype "passive"))
      (node (ref "C4") (pin "2") (pinfunction "2_2") (pintype "passive"))
      (node (ref "C5") (pin "2") (pinfunction "2_2") (pintype "passive"))
      (node (ref "C6") (pin "-") (pinfunction "-_-") (pintype "passive"))
      (node (ref "C7") (pin "2") (pinfunction "2_2") (pintype "passive"))
      (node (ref "C8") (pin "2") (pinfunction "2_2") (pintype "passive"))
      (node (ref "C9") (pin "2") (pinfunction "2_2") (pintype "passive"))
      (node (ref "D5") (pin "A") (pinfunction "A_A") (pintype "passive"))
      (node (ref "D6") (pin "A") (pinfunction "A_A") (pintype "passive"))
      (node (ref "G1") (pin "GND3") (pinfunction "GND3_GND3") (pintype "power_in"))
      (node (ref "G1") (pin "GND5") (pinfunction "GND5_GND5") (pintype "power_in"))
      (node (ref "G1") (pin "GND6") (pinfunction "GND6_GND6") (pintype "power_in"))
      (node (ref "G1") (pin "GND7") (pinfunction "GND7_GND7") (pintype "power_in"))
      (node (ref "G1") (pin "GND8") (pinfunction "GND8_GND8") (pintype "power_in"))
      (node (ref "IC1") (pin "2") (pinfunction "GNDSIG_2") (pintype "input"))
      (node (ref "IC1") (pin "3") (pinfunction "~{ON/OFF}_3") (pintype "input"))
      (node (ref "IC1") (pin "4") (pinfunction "GND_4") (pintype "power_in"))
      (node (ref "IC2") (pin "2") (pinfunction "VSS_2") (pintype "power_in"))
      (node (ref "J1") (pin "2") (pinfunction "2_2") (pintype "passive"))
      (node (ref "J1") (pin "3") (pinfunction "3_3") (pintype "passive"))
      (node (ref "JP1") (pin "5") (pinfunction "5_5") (pintype "passive"))
      (node (ref "JP1") (pin "6") (pinfunction "6_6") (pintype "passive"))
      (node (ref "JP10") (pin "5") (pinfunction "5_5") (pintype "passive"))
      (node (ref "JP2") (pin "5") (pinfunction "5_5") (pintype "passive"))
      (node (ref "JP2") (pin "6") (pinfunction "6_6") (pintype "passive"))
      (node (ref "JP3") (pin "5") (pinfunction "5_5") (pintype "passive"))
      (node (ref "JP3") (pin "6") (pinfunction "6_6") (pintype "passive"))
      (node (ref "JP4") (pin "5") (pinfunction "5_5") (pintype "passive"))
      (node (ref "JP4") (pin "6") (pinfunction "6_6") (pintype "passive"))
      (node (ref "JP5") (pin "8") (pinfunction "8_8") (pintype "passive"))
      (node (ref "JP6") (pin "4") (pinfunction "4_4") (pintype "passive"))
      (node (ref "JP8") (pin "5") (pinfunction "5_5") (pintype "passive"))
      (node (ref "JP9") (pin "5") (pinfunction "5_5") (pintype "passive"))
      (node (ref "Q1") (pin "2") (pinfunction "S_2") (pintype "passive"))
      (node (ref "Q10") (pin "2") (pinfunction "S_2") (pintype "passive"))
      (node (ref "Q11") (pin "2") (pinfunction "S_2") (pintype "passive"))
      (node (ref "Q12") (pin "2") (pinfunction "S_2") (pintype "passive"))
      (node (ref "Q13") (pin "2") (pinfunction "S_2") (pintype "passive"))
      (node (ref "Q14") (pin "2") (pinfunction "S_2") (pintype "passive"))
      (node (ref "Q15") (pin "2") (pinfunction "S_2") (pintype "passive"))
      (node (ref "Q16") (pin "2") (pinfunction "S_2") (pintype "passive"))
      (node (ref "Q2") (pin "2") (pinfunction "S_2") (pintype "passive"))
      (node (ref "Q3") (pin "2") (pinfunction "S_2") (pintype "passive"))
      (node (ref "Q4") (pin "2") (pinfunction "S_2") (pintype "passive"))
      (node (ref "Q5") (pin "2") (pinfunction "S_2") (pintype "passive"))
      (node (ref "Q6") (pin "2") (pinfunction "S_2") (pintype "passive"))
      (node (ref "Q7") (pin "2") (pinfunction "S_2") (pintype "passive"))
      (node (ref "Q8") (pin "2") (pinfunction "S_2") (pintype "passive"))
      (node (ref "Q9") (pin "2") (pinfunction "S_2") (pintype "passive"))
      (node (ref "R16") (pin "2") (pinfunction "2_2") (pintype "passive"))
      (node (ref "R51") (pin "1") (pinfunction "1_1") (pintype "passive"))
      (node (ref "SJ12") (pin "2") (pinfunction "2_2") (pintype "passive"))
      (node (ref "SJ13") (pin "P$2") (pinfunction "2_P$2") (pintype "passive"))
      (node (ref "SJ19") (pin "2") (pinfunction "2_2") (pintype "passive"))
      (node (ref "SJ20") (pin "P$2") (pinfunction "2_P$2") (pintype "passive"))
      (node (ref "U1") (pin "2") (pinfunction "GND_2") (pintype "power_in"))
      (node (ref "U10") (pin "3") (pinfunction "VSS_3") (pintype "power_in"))
      (node (ref "U11") (pin "13") (pinfunction "G_13") (pintype "input"))
      (node (ref "U11") (pin "8") (pinfunction "GND_8") (pintype "power_in"))
      (node (ref "U13") (pin "13") (pinfunction "G_13") (pintype "input"))
      (node (ref "U13") (pin "8") (pinfunction "GND_8") (pintype "power_in"))
      (node (ref "U2") (pin "4") (pinfunction "SD_4") (pintype "bidirectional"))
      (node (ref "U2") (pin "5") (pinfunction "GND1_5") (pintype "power_in"))
      (node (ref "U2") (pin "6") (pinfunction "GND2_6") (pintype "power_in"))
      (node (ref "U2") (pin "7") (pinfunction "GND3_7") (pintype "power_in"))
      (node (ref "U2") (pin "8") (pinfunction "GND4_8") (pintype "power_in"))
      (node (ref "U3") (pin "6") (pinfunction "INH_6") (pintype "input"))
      (node (ref "U3") (pin "8") (pinfunction "GND_8") (pintype "power_in"))
      (node (ref "U4") (pin "6") (pinfunction "INH_6") (pintype "input"))
      (node (ref "U4") (pin "8") (pinfunction "GND_8") (pintype "power_in"))
      (node (ref "U5") (pin "3") (pinfunction "VSS_3") (pintype "power_in"))
      (node (ref "U6") (pin "11") (pinfunction "V-_11") (pintype "power_in"))
      (node (ref "U7") (pin "3") (pinfunction "VSS_3") (pintype "power_in"))
      (node (ref "U8") (pin "3") (pinfunction "VSS_3") (pintype "power_in"))
      (node (ref "U9") (pin "11") (pinfunction "V-_11") (pintype "power_in"))
      (node (ref "X1") (pin "3") (pinfunction "3_3") (pintype "passive"))
      (node (ref "X1") (pin "6") (pinfunction "6_6") (pintype "passive"))
      (node (ref "X1") (pin "7") (pinfunction "7_7") (pintype "passive"))
      (node (ref "X2") (pin "3") (pinfunction "3_3") (pintype "passive"))
      (node (ref "X2") (pin "6") (pinfunction "6_6") (pintype "passive"))
      (node (ref "X2") (pin "7") (pinfunction "7_7") (pintype "passive"))
      (node (ref "X3") (pin "2") (pinfunction "2_2") (pintype "passive"))
      (node (ref "X5") (pin "9") (pinfunction "9_9") (pintype "passive"))
      (node (ref "X6") (pin "2") (pinfunction "2_2") (pintype "passive"))
    )
    (net (code "18") (name "I2CSCL") (class "Default")
      (node (ref "G1") (pin "PB6") (pinfunction "PB6_PB6") (pintype "bidirectional"))
      (node (ref "JP6") (pin "1") (pinfunction "1_1") (pintype "passive"))
      (node (ref "R15") (pin "2") (pinfunction "2_2") (pintype "passive"))
    )
    (net (code "19") (name "I2CSDA") (class "Default")
      (node (ref "G1") (pin "PB7") (pinfunction "PB7_PB7") (pintype "bidirectional"))
      (node (ref "JP6") (pin "2") (pinfunction "2_2") (pintype "passive"))
      (node (ref "R14") (pin "2") (pinfunction "2_2") (pintype "passive"))
    )
    (net (code "20") (name "ILAT") (class "Default")
      (node (ref "G1") (pin "PA6") (pinfunction "PA6_PA6") (pintype "bidirectional"))
      (node (ref "U3") (pin "15") (pinfunction "SH/~{LD}_15") (pintype "input"))
      (node (ref "U4") (pin "15") (pinfunction "SH/~{LD}_15") (pintype "input"))
    )
    (net (code "21") (name "MISO") (class "Default")
      (node (ref "G1") (pin "PB4") (pinfunction "PB4_PB4") (pintype "bidirectional"))
      (node (ref "JP5") (pin "1") (pinfunction "1_1") (pintype "passive"))
    )
    (net (code "22") (name "MISO2") (class "Default")
      (node (ref "G1") (pin "PC2") (pinfunction "PC2_PC2") (pintype "bidirectional"))
      (node (ref "SJ1") (pin "P$2") (pinfunction "2_P$2") (pintype "passive"))
      (node (ref "SJ7") (pin "P$2") (pinfunction "2_P$2") (pintype "passive"))
      (node (ref "U3") (pin "13") (pinfunction "QH_13") (pintype "output"))
    )
    (net (code "23") (name "MOSI") (class "Default")
      (node (ref "G1") (pin "PB5") (pinfunction "PB5_PB5") (pintype "bidirectional"))
      (node (ref "R4") (pin "1") (pinfunction "1_1") (pintype "passive"))
      (node (ref "SJ14") (pin "P$2") (pinfunction "2_P$2") (pintype "passive"))
      (node (ref "SJ4") (pin "1") (pinfunction "1_1") (pintype "passive"))
      (node (ref "U13") (pin "14") (pinfunction "SER_14") (pintype "input"))
    )
    (net (code "24") (name "Net-(D1-PadA)") (class "Default")
      (node (ref "D1") (pin "A") (pinfunction "A_A") (pintype "passive"))
      (node (ref "D2") (pin "A") (pinfunction "A_A") (pintype "passive"))
      (node (ref "JP7") (pin "4") (pinfunction "4_4") (pintype "passive"))
    )
    (net (code "25") (name "Net-(D1-PadC)") (class "Default")
      (node (ref "D1") (pin "C") (pinfunction "C_C") (pintype "passive"))
      (node (ref "D2") (pin "C") (pinfunction "C_C") (pintype "passive"))
      (node (ref "JP7") (pin "1") (pinfunction "1_1") (pintype "passive"))
    )
    (net (code "26") (name "Net-(D3-PadA)") (class "Default")
      (node (ref "D3") (pin "A") (pinfunction "A_A") (pintype "passive"))
      (node (ref "D4") (pin "A") (pinfunction "A_A") (pintype "passive"))
      (node (ref "J1") (pin "1") (pinfunction "1_1") (pintype "passive"))
      (node (ref "X3") (pin "1") (pinfunction "1_1") (pintype "passive"))
    )
    (net (code "27") (name "Net-(IC1-OUT)") (class "Default")
      (node (ref "D5") (pin "C") (pinfunction "C_C") (pintype "passive"))
      (node (ref "D6") (pin "C") (pinfunction "C_C") (pintype "passive"))
      (node (ref "IC1") (pin "7") (pinfunction "OUT_7") (pintype "passive"))
      (node (ref "L1") (pin "2") (pinfunction "2_2") (pintype "passive"))
      (node (ref "U2") (pin "2") (pinfunction "VOUT_2") (pintype "bidirectional"))
    )
    (net (code "28") (name "Net-(IC2-RS)") (class "Default")
      (node (ref "IC2") (pin "8") (pinfunction "RS_8") (pintype "bidirectional"))
      (node (ref "R16") (pin "1") (pinfunction "1_1") (pintype "passive"))
      (node (ref "U1") (pin "8") (pinfunction "RS_8") (pintype "input"))
    )
    (net (code "29") (name "Net-(IC2-VREF)") (class "Default")
      (node (ref "IC2") (pin "5") (pinfunction "VREF_5") (pintype "bidirectional"))
      (node (ref "SJ6") (pin "P$2") (pinfunction "2_P$2") (pintype "passive"))
      (node (ref "U1") (pin "5") (pinfunction "VREF_5") (pintype "output"))
    )
    (net (code "30") (name "Net-(JP7-Pad3)") (class "Default")
      (node (ref "JP7") (pin "3") (pinfunction "3_3") (pintype "passive"))
      (node (ref "R17") (pin "1") (pinfunction "1_1") (pintype "passive"))
    )
    (net (code "31") (name "Net-(JP8-Pad10)") (class "Default")
      (node (ref "JP8") (pin "10") (pinfunction "10_10") (pintype "passive"))
      (node (ref "R25") (pin "2") (pinfunction "2_2") (pintype "passive"))
      (node (ref "R26") (pin "2") (pinfunction "2_2") (pintype "passive"))
      (node (ref "RN1") (pin "9") (pinfunction "9_9") (pintype "passive"))
      (node (ref "RN2") (pin "1") (pinfunction "1_1") (pintype "passive"))
      (node (ref "X4") (pin "1") (pinfunction "1_1") (pintype "passive"))
    )
    (net (code "32") (name "Net-(JP9-Pad10)") (class "Default")
      (node (ref "JP9") (pin "10") (pinfunction "10_10") (pintype "passive"))
      (node (ref "R41") (pin "2") (pinfunction "2_2") (pintype "passive"))
      (node (ref "R42") (pin "2") (pinfunction "2_2") (pintype "passive"))
      (node (ref "RN3") (pin "9") (pinfunction "9_9") (pintype "passive"))
      (node (ref "RN4") (pin "1") (pinfunction "1_1") (pintype "passive"))
      (node (ref "X5") (pin "1") (pinfunction "1_1") (pintype "passive"))
    )
    (net (code "33") (name "Net-(Q1-D)") (class "Default")
      (node (ref "Q1") (pin "3") (pinfunction "D_3") (pintype "passive"))
      (node (ref "U12") (pin "11") (pinfunction "O8_11") (pintype "open_collector"))
      (node (ref "X8") (pin "8") (pinfunction "8_8") (pintype "passive"))
    )
    (net (code "34") (name "Net-(Q1-G)") (class "Default")
      (node (ref "Q1") (pin "1") (pinfunction "G_1") (pintype "passive"))
      (node (ref "R52") (pin "2") (pinfunction "2_2") (pintype "passive"))
    )
    (net (code "35") (name "Net-(Q2-D)") (class "Default")
      (node (ref "Q2") (pin "3") (pinfunction "D_3") (pintype "passive"))
      (node (ref "U12") (pin "12") (pinfunction "O7_12") (pintype "open_collector"))
      (node (ref "X8") (pin "7") (pinfunction "7_7") (pintype "passive"))
    )
    (net (code "36") (name "Net-(Q2-G)") (class "Default")
      (node (ref "Q2") (pin "1") (pinfunction "G_1") (pintype "passive"))
      (node (ref "R53") (pin "2") (pinfunction "2_2") (pintype "passive"))
    )
    (net (code "37") (name "Net-(Q3-D)") (class "Default")
      (node (ref "Q3") (pin "3") (pinfunction "D_3") (pintype "passive"))
      (node (ref "U12") (pin "13") (pinfunction "O6_13") (pintype "open_collector"))
      (node (ref "X8") (pin "6") (pinfunction "6_6") (pintype "passive"))
    )
    (net (code "38") (name "Net-(Q3-G)") (class "Default")
      (node (ref "Q3") (pin "1") (pinfunction "G_1") (pintype "passive"))
      (node (ref "R54") (pin "2") (pinfunction "2_2") (pintype "passive"))
    )
    (net (code "39") (name "Net-(Q4-D)") (class "Default")
      (node (ref "Q4") (pin "3") (pinfunction "D_3") (pintype "passive"))
      (node (ref "U12") (pin "14") (pinfunction "O5_14") (pintype "open_collector"))
      (node (ref "X8") (pin "5") (pinfunction "5_5") (pintype "passive"))
    )
    (net (code "40") (name "Net-(Q4-G)") (class "Default")
      (node (ref "Q4") (pin "1") (pinfunction "G_1") (pintype "passive"))
      (node (ref "R55") (pin "2") (pinfunction "2_2") (pintype "passive"))
    )
    (net (code "41") (name "Net-(Q5-D)") (class "Default")
      (node (ref "Q5") (pin "3") (pinfunction "D_3") (pintype "passive"))
      (node (ref "U12") (pin "15") (pinfunction "O4_15") (pintype "open_collector"))
      (node (ref "X8") (pin "4") (pinfunction "4_4") (pintype "passive"))
    )
    (net (code "42") (name "Net-(Q5-G)") (class "Default")
      (node (ref "Q5") (pin "1") (pinfunction "G_1") (pintype "passive"))
      (node (ref "R56") (pin "2") (pinfunction "2_2") (pintype "passive"))
    )
    (net (code "43") (name "Net-(Q6-D)") (class "Default")
      (node (ref "Q6") (pin "3") (pinfunction "D_3") (pintype "passive"))
      (node (ref "U12") (pin "16") (pinfunction "O3_16") (pintype "open_collector"))
      (node (ref "X8") (pin "3") (pinfunction "3_3") (pintype "passive"))
    )
    (net (code "44") (name "Net-(Q6-G)") (class "Default")
      (node (ref "Q6") (pin "1") (pinfunction "G_1") (pintype "passive"))
      (node (ref "R57") (pin "2") (pinfunction "2_2") (pintype "passive"))
    )
    (net (code "45") (name "Net-(Q7-D)") (class "Default")
      (node (ref "Q7") (pin "3") (pinfunction "D_3") (pintype "passive"))
      (node (ref "U12") (pin "17") (pinfunction "O2_17") (pintype "open_collector"))
      (node (ref "X8") (pin "2") (pinfunction "2_2") (pintype "passive"))
    )
    (net (code "46") (name "Net-(Q7-G)") (class "Default")
      (node (ref "Q7") (pin "1") (pinfunction "G_1") (pintype "passive"))
      (node (ref "R58") (pin "2") (pinfunction "2_2") (pintype "passive"))
    )
    (net (code "47") (name "Net-(Q8-D)") (class "Default")
      (node (ref "Q8") (pin "3") (pinfunction "D_3") (pintype "passive"))
      (node (ref "U12") (pin "18") (pinfunction "O1_18") (pintype "open_collector"))
      (node (ref "X8") (pin "1") (pinfunction "1_1") (pintype "passive"))
    )
    (net (code "48") (name "Net-(Q8-G)") (class "Default")
      (node (ref "Q8") (pin "1") (pinfunction "G_1") (pintype "passive"))
      (node (ref "R59") (pin "2") (pinfunction "2_2") (pintype "passive"))
    )
    (net (code "49") (name "Net-(Q9-D)") (class "Default")
      (node (ref "Q9") (pin "3") (pinfunction "D_3") (pintype "passive"))
      (node (ref "U14") (pin "11") (pinfunction "O8_11") (pintype "open_collector"))
      (node (ref "X9") (pin "8") (pinfunction "8_8") (pintype "passive"))
    )
    (net (code "50") (name "Net-(Q9-G)") (class "Default")
      (node (ref "Q9") (pin "1") (pinfunction "G_1") (pintype "passive"))
      (node (ref "R60") (pin "2") (pinfunction "2_2") (pintype "passive"))
    )
    (net (code "51") (name "Net-(Q10-D)") (class "Default")
      (node (ref "Q10") (pin "3") (pinfunction "D_3") (pintype "passive"))
      (node (ref "U14") (pin "12") (pinfunction "O7_12") (pintype "open_collector"))
      (node (ref "X9") (pin "7") (pinfunction "7_7") (pintype "passive"))
    )
    (net (code "52") (name "Net-(Q10-G)") (class "Default")
      (node (ref "Q10") (pin "1") (pinfunction "G_1") (pintype "passive"))
      (node (ref "R61") (pin "2") (pinfunction "2_2") (pintype "passive"))
    )
    (net (code "53") (name "Net-(Q11-D)") (class "Default")
      (node (ref "Q11") (pin "3") (pinfunction "D_3") (pintype "passive"))
      (node (ref "U14") (pin "13") (pinfunction "O6_13") (pintype "open_collector"))
      (node (ref "X9") (pin "6") (pinfunction "6_6") (pintype "passive"))
    )
    (net (code "54") (name "Net-(Q11-G)") (class "Default")
      (node (ref "Q11") (pin "1") (pinfunction "G_1") (pintype "passive"))
      (node (ref "R62") (pin "2") (pinfunction "2_2") (pintype "passive"))
    )
    (net (code "55") (name "Net-(Q12-D)") (class "Default")
      (node (ref "Q12") (pin "3") (pinfunction "D_3") (pintype "passive"))
      (node (ref "U14") (pin "14") (pinfunction "O5_14") (pintype "open_collector"))
      (node (ref "X9") (pin "5") (pinfunction "5_5") (pintype "passive"))
    )
    (net (code "56") (name "Net-(Q12-G)") (class "Default")
      (node (ref "Q12") (pin "1") (pinfunction "G_1") (pintype "passive"))
      (node (ref "R63") (pin "2") (pinfunction "2_2") (pintype "passive"))
    )
    (net (code "57") (name "Net-(Q13-D)") (class "Default")
      (node (ref "Q13") (pin "3") (pinfunction "D_3") (pintype "passive"))
      (node (ref "U14") (pin "15") (pinfunction "O4_15") (pintype "open_collector"))
      (node (ref "X9") (pin "4") (pinfunction "4_4") (pintype "passive"))
    )
    (net (code "58") (name "Net-(Q13-G)") (class "Default")
      (node (ref "Q13") (pin "1") (pinfunction "G_1") (pintype "passive"))
      (node (ref "R64") (pin "2") (pinfunction "2_2") (pintype "passive"))
    )
    (net (code "59") (name "Net-(Q14-D)") (class "Default")
      (node (ref "Q14") (pin "3") (pinfunction "D_3") (pintype "passive"))
      (node (ref "U14") (pin "16") (pinfunction "O3_16") (pintype "open_collector"))
      (node (ref "X9") (pin "3") (pinfunction "3_3") (pintype "passive"))
    )
    (net (code "60") (name "Net-(Q14-G)") (class "Default")
      (node (ref "Q14") (pin "1") (pinfunction "G_1") (pintype "passive"))
      (node (ref "R65") (pin "2") (pinfunction "2_2") (pintype "passive"))
    )
    (net (code "61") (name "Net-(Q15-D)") (class "Default")
      (node (ref "Q15") (pin "3") (pinfunction "D_3") (pintype "passive"))
      (node (ref "U14") (pin "17") (pinfunction "O2_17") (pintype "open_collector"))
      (node (ref "X9") (pin "2") (pinfunction "2_2") (pintype "passive"))
    )
    (net (code "62") (name "Net-(Q15-G)") (class "Default")
      (node (ref "Q15") (pin "1") (pinfunction "G_1") (pintype "passive"))
      (node (ref "R66") (pin "2") (pinfunction "2_2") (pintype "passive"))
    )
    (net (code "63") (name "Net-(Q16-D)") (class "Default")
      (node (ref "Q16") (pin "3") (pinfunction "D_3") (pintype "passive"))
      (node (ref "U14") (pin "18") (pinfunction "O1_18") (pintype "open_collector"))
      (node (ref "X9") (pin "1") (pinfunction "1_1") (pintype "passive"))
    )
    (net (code "64") (name "Net-(Q16-G)") (class "Default")
      (node (ref "Q16") (pin "1") (pinfunction "G_1") (pintype "passive"))
      (node (ref "R67") (pin "2") (pinfunction "2_2") (pintype "passive"))
    )
    (net (code "65") (name "Net-(RN2A-2)") (class "Default")
      (node (ref "R25") (pin "1") (pinfunction "1_1") (pintype "passive"))
      (node (ref "RN2") (pin "16") (pinfunction "2_16") (pintype "passive"))
      (node (ref "U3") (pin "14") (pinfunction "H_14") (pintype "input"))
    )
    (net (code "66") (name "Net-(RN2B-1)") (class "Default")
      (node (ref "JP8") (pin "9") (pinfunction "9_9") (pintype "passive"))
      (node (ref "R24") (pin "2") (pinfunction "2_2") (pintype "passive"))
      (node (ref "R27") (pin "2") (pinfunction "2_2") (pintype "passive"))
      (node (ref "RN1") (pin "8") (pinfunction "8_8") (pintype "passive"))
      (node (ref "RN2") (pin "2") (pinfunction "1_2") (pintype "passive"))
      (node (ref "X4") (pin "2") (pinfunction "2_2") (pintype "passive"))
    )
    (net (code "67") (name "Net-(RN2B-2)") (class "Default")
      (node (ref "R24") (pin "1") (pinfunction "1_1") (pintype "passive"))
      (node (ref "RN2") (pin "15") (pinfunction "2_15") (pintype "passive"))
      (node (ref "U3") (pin "12") (pinfunction "G_12") (pintype "input"))
    )
    (net (code "68") (name "Net-(RN2C-1)") (class "Default")
      (node (ref "JP8") (pin "8") (pinfunction "8_8") (pintype "passive"))
      (node (ref "R23") (pin "2") (pinfunction "2_2") (pintype "passive"))
      (node (ref "R28") (pin "2") (pinfunction "2_2") (pintype "passive"))
      (node (ref "RN1") (pin "7") (pinfunction "7_7") (pintype "passive"))
      (node (ref "RN2") (pin "3") (pinfunction "1_3") (pintype "passive"))
      (node (ref "X4") (pin "3") (pinfunction "3_3") (pintype "passive"))
    )
    (net (code "69") (name "Net-(RN2C-2)") (class "Default")
      (node (ref "R23") (pin "1") (pinfunction "1_1") (pintype "passive"))
      (node (ref "RN2") (pin "14") (pinfunction "2_14") (pintype "passive"))
      (node (ref "U3") (pin "11") (pinfunction "F_11") (pintype "input"))
    )
    (net (code "70") (name "Net-(RN2D-1)") (class "Default")
      (node (ref "JP8") (pin "7") (pinfunction "7_7") (pintype "passive"))
      (node (ref "R22") (pin "2") (pinfunction "2_2") (pintype "passive"))
      (node (ref "R29") (pin "2") (pinfunction "2_2") (pintype "passive"))
      (node (ref "RN1") (pin "6") (pinfunction "6_6") (pintype "passive"))
      (node (ref "RN2") (pin "4") (pinfunction "1_4") (pintype "passive"))
      (node (ref "X4") (pin "4") (pinfunction "4_4") (pintype "passive"))
    )
    (net (code "71") (name "Net-(RN2D-2)") (class "Default")
      (node (ref "R22") (pin "1") (pinfunction "1_1") (pintype "passive"))
      (node (ref "RN2") (pin "13") (pinfunction "2_13") (pintype "passive"))
      (node (ref "U3") (pin "10") (pinfunction "E_10") (pintype "input"))
    )
    (net (code "72") (name "Net-(RN2E-1)") (class "Default")
      (node (ref "JP8") (pin "4") (pinfunction "4_4") (pintype "passive"))
      (node (ref "R21") (pin "2") (pinfunction "2_2") (pintype "passive"))
      (node (ref "R30") (pin "2") (pinfunction "2_2") (pintype "passive"))
      (node (ref "RN1") (pin "5") (pinfunction "5_5") (pintype "passive"))
      (node (ref "RN2") (pin "5") (pinfunction "1_5") (pintype "passive"))
      (node (ref "X4") (pin "5") (pinfunction "5_5") (pintype "passive"))
    )
    (net (code "73") (name "Net-(RN2E-2)") (class "Default")
      (node (ref "R21") (pin "1") (pinfunction "1_1") (pintype "passive"))
      (node (ref "RN2") (pin "12") (pinfunction "2_12") (pintype "passive"))
      (node (ref "U3") (pin "5") (pinfunction "D_5") (pintype "input"))
    )
    (net (code "74") (name "Net-(RN2F-1)") (class "Default")
      (node (ref "JP8") (pin "3") (pinfunction "3_3") (pintype "passive"))
      (node (ref "R20") (pin "2") (pinfunction "2_2") (pintype "passive"))
      (node (ref "R31") (pin "2") (pinfunction "2_2") (pintype "passive"))
      (node (ref "RN1") (pin "4") (pinfunction "4_4") (pintype "passive"))
      (node (ref "RN2") (pin "6") (pinfunction "1_6") (pintype "passive"))
      (node (ref "X4") (pin "6") (pinfunction "6_6") (pintype "passive"))
    )
    (net (code "75") (name "Net-(RN2F-2)") (class "Default")
      (node (ref "R20") (pin "1") (pinfunction "1_1") (pintype "passive"))
      (node (ref "RN2") (pin "11") (pinfunction "2_11") (pintype "passive"))
      (node (ref "U3") (pin "4") (pinfunction "C_4") (pintype "input"))
    )
    (net (code "76") (name "Net-(RN2G-1)") (class "Default")
      (node (ref "JP8") (pin "2") (pinfunction "2_2") (pintype "passive"))
      (node (ref "R19") (pin "2") (pinfunction "2_2") (pintype "passive"))
      (node (ref "R32") (pin "2") (pinfunction "2_2") (pintype "passive"))
      (node (ref "RN1") (pin "3") (pinfunction "3_3") (pintype "passive"))
      (node (ref "RN2") (pin "7") (pinfunction "1_7") (pintype "passive"))
      (node (ref "X4") (pin "7") (pinfunction "7_7") (pintype "passive"))
    )
    (net (code "77") (name "Net-(RN2G-2)") (class "Default")
      (node (ref "R19") (pin "1") (pinfunction "1_1") (pintype "passive"))
      (node (ref "RN2") (pin "10") (pinfunction "2_10") (pintype "passive"))
      (node (ref "U3") (pin "3") (pinfunction "B_3") (pintype "input"))
    )
    (net (code "78") (name "Net-(RN2H-1)") (class "Default")
      (node (ref "JP8") (pin "1") (pinfunction "1_1") (pintype "passive"))
      (node (ref "R18") (pin "2") (pinfunction "2_2") (pintype "passive"))
      (node (ref "R33") (pin "2") (pinfunction "2_2") (pintype "passive"))
      (node (ref "RN1") (pin "2") (pinfunction "2_2") (pintype "passive"))
      (node (ref "RN2") (pin "8") (pinfunction "1_8") (pintype "passive"))
      (node (ref "X4") (pin "8") (pinfunction "8_8") (pintype "passive"))
    )
    (net (code "79") (name "Net-(RN2H-2)") (class "Default")
      (node (ref "R18") (pin "1") (pinfunction "1_1") (pintype "passive"))
      (node (ref "RN2") (pin "9") (pinfunction "2_9") (pintype "passive"))
      (node (ref "U3") (pin "2") (pinfunction "A_2") (pintype "input"))
    )
    (net (code "80") (name "Net-(RN4A-2)") (class "Default")
      (node (ref "R41") (pin "1") (pinfunction "1_1") (pintype "passive"))
      (node (ref "RN4") (pin "16") (pinfunction "2_16") (pintype "passive"))
      (node (ref "U4") (pin "14") (pinfunction "H_14") (pintype "input"))
    )
    (net (code "81") (name "Net-(RN4B-1)") (class "Default")
      (node (ref "JP9") (pin "9") (pinfunction "9_9") (pintype "passive"))
      (node (ref "R40") (pin "2") (pinfunction "2_2") (pintype "passive"))
      (node (ref "R43") (pin "2") (pinfunction "2_2") (pintype "passive"))
      (node (ref "RN3") (pin "8") (pinfunction "8_8") (pintype "passive"))
      (node (ref "RN4") (pin "2") (pinfunction "1_2") (pintype "passive"))
      (node (ref "X5") (pin "2") (pinfunction "2_2") (pintype "passive"))
    )
    (net (code "82") (name "Net-(RN4B-2)") (class "Default")
      (node (ref "R40") (pin "1") (pinfunction "1_1") (pintype "passive"))
      (node (ref "RN4") (pin "15") (pinfunction "2_15") (pintype "passive"))
      (node (ref "U4") (pin "12") (pinfunction "G_12") (pintype "input"))
    )
    (net (code "83") (name "Net-(RN4C-1)") (class "Default")
      (node (ref "JP9") (pin "8") (pinfunction "8_8") (pintype "passive"))
      (node (ref "R39") (pin "2") (pinfunction "2_2") (pintype "passive"))
      (node (ref "R44") (pin "2") (pinfunction "2_2") (pintype "passive"))
      (node (ref "RN3") (pin "7") (pinfunction "7_7") (pintype "passive"))
      (node (ref "RN4") (pin "3") (pinfunction "1_3") (pintype "passive"))
      (node (ref "X5") (pin "3") (pinfunction "3_3") (pintype "passive"))
    )
    (net (code "84") (name "Net-(RN4C-2)") (class "Default")
      (node (ref "R39") (pin "1") (pinfunction "1_1") (pintype "passive"))
      (node (ref "RN4") (pin "14") (pinfunction "2_14") (pintype "passive"))
      (node (ref "U4") (pin "11") (pinfunction "F_11") (pintype "input"))
    )
    (net (code "85") (name "Net-(RN4D-1)") (class "Default")
      (node (ref "JP9") (pin "7") (pinfunction "7_7") (pintype "passive"))
      (node (ref "R38") (pin "2") (pinfunction "2_2") (pintype "passive"))
      (node (ref "R45") (pin "2") (pinfunction "2_2") (pintype "passive"))
      (node (ref "RN3") (pin "6") (pinfunction "6_6") (pintype "passive"))
      (node (ref "RN4") (pin "4") (pinfunction "1_4") (pintype "passive"))
      (node (ref "X5") (pin "4") (pinfunction "4_4") (pintype "passive"))
    )
    (net (code "86") (name "Net-(RN4D-2)") (class "Default")
      (node (ref "R38") (pin "1") (pinfunction "1_1") (pintype "passive"))
      (node (ref "RN4") (pin "13") (pinfunction "2_13") (pintype "passive"))
      (node (ref "U4") (pin "10") (pinfunction "E_10") (pintype "input"))
    )
    (net (code "87") (name "Net-(RN4E-1)") (class "Default")
      (node (ref "JP9") (pin "4") (pinfunction "4_4") (pintype "passive"))
      (node (ref "R37") (pin "2") (pinfunction "2_2") (pintype "passive"))
      (node (ref "R46") (pin "2") (pinfunction "2_2") (pintype "passive"))
      (node (ref "RN3") (pin "5") (pinfunction "5_5") (pintype "passive"))
      (node (ref "RN4") (pin "5") (pinfunction "1_5") (pintype "passive"))
      (node (ref "X5") (pin "5") (pinfunction "5_5") (pintype "passive"))
    )
    (net (code "88") (name "Net-(RN4E-2)") (class "Default")
      (node (ref "R37") (pin "1") (pinfunction "1_1") (pintype "passive"))
      (node (ref "RN4") (pin "12") (pinfunction "2_12") (pintype "passive"))
      (node (ref "U4") (pin "5") (pinfunction "D_5") (pintype "input"))
    )
    (net (code "89") (name "Net-(RN4F-1)") (class "Default")
      (node (ref "JP9") (pin "3") (pinfunction "3_3") (pintype "passive"))
      (node (ref "R36") (pin "2") (pinfunction "2_2") (pintype "passive"))
      (node (ref "R47") (pin "2") (pinfunction "2_2") (pintype "passive"))
      (node (ref "RN3") (pin "4") (pinfunction "4_4") (pintype "passive"))
      (node (ref "RN4") (pin "6") (pinfunction "1_6") (pintype "passive"))
      (node (ref "X5") (pin "6") (pinfunction "6_6") (pintype "passive"))
    )
    (net (code "90") (name "Net-(RN4F-2)") (class "Default")
      (node (ref "R36") (pin "1") (pinfunction "1_1") (pintype "passive"))
      (node (ref "RN4") (pin "11") (pinfunction "2_11") (pintype "passive"))
      (node (ref "U4") (pin "4") (pinfunction "C_4") (pintype "input"))
    )
    (net (code "91") (name "Net-(RN4G-1)") (class "Default")
      (node (ref "JP9") (pin "2") (pinfunction "2_2") (pintype "passive"))
      (node (ref "R35") (pin "2") (pinfunction "2_2") (pintype "passive"))
      (node (ref "R48") (pin "2") (pinfunction "2_2") (pintype "passive"))
      (node (ref "RN3") (pin "3") (pinfunction "3_3") (pintype "passive"))
      (node (ref "RN4") (pin "7") (pinfunction "1_7") (pintype "passive"))
      (node (ref "X5") (pin "7") (pinfunction "7_7") (pintype "passive"))
    )
    (net (code "92") (name "Net-(RN4G-2)") (class "Default")
      (node (ref "R35") (pin "1") (pinfunction "1_1") (pintype "passive"))
      (node (ref "RN4") (pin "10") (pinfunction "2_10") (pintype "passive"))
      (node (ref "U4") (pin "3") (pinfunction "B_3") (pintype "input"))
    )
    (net (code "93") (name "Net-(RN4H-1)") (class "Default")
      (node (ref "JP9") (pin "1") (pinfunction "1_1") (pintype "passive"))
      (node (ref "R34") (pin "2") (pinfunction "2_2") (pintype "passive"))
      (node (ref "R49") (pin "2") (pinfunction "2_2") (pintype "passive"))
      (node (ref "RN3") (pin "2") (pinfunction "2_2") (pintype "passive"))
      (node (ref "RN4") (pin "8") (pinfunction "1_8") (pintype "passive"))
      (node (ref "X5") (pin "8") (pinfunction "8_8") (pintype "passive"))
    )
    (net (code "94") (name "Net-(RN4H-2)") (class "Default")
      (node (ref "R34") (pin "1") (pinfunction "1_1") (pintype "passive"))
      (node (ref "RN4") (pin "9") (pinfunction "2_9") (pintype "passive"))
      (node (ref "U4") (pin "2") (pinfunction "A_2") (pintype "input"))
    )
    (net (code "95") (name "Net-(SJ1-1)") (class "Default")
      (node (ref "G1") (pin "PB14") (pinfunction "PB14_PB14") (pintype "bidirectional"))
      (node (ref "SJ1") (pin "P$1") (pinfunction "1_P$1") (pintype "passive"))
    )
    (net (code "96") (name "Net-(SJ2-2)") (class "Default")
      (node (ref "G1") (pin "PB13") (pinfunction "PB13_PB13") (pintype "bidirectional"))
      (node (ref "SJ2") (pin "P$2") (pinfunction "2_P$2") (pintype "passive"))
    )
    (net (code "97") (name "Net-(SJ3-1)") (class "Default")
      (node (ref "G1") (pin "VIN2") (pinfunction "VIN2_VIN2") (pintype "power_in"))
      (node (ref "SJ3") (pin "P$1") (pinfunction "1_P$1") (pintype "passive"))
    )
    (net (code "98") (name "Net-(SJ5-2)") (class "Default")
      (node (ref "JP5") (pin "2") (pinfunction "2_2") (pintype "passive"))
      (node (ref "SJ4") (pin "2") (pinfunction "2_2") (pintype "passive"))
      (node (ref "SJ5") (pin "P$2") (pinfunction "2_P$2") (pintype "passive"))
    )
    (net (code "99") (name "Net-(SJ10-1)") (class "Default")
      (node (ref "SJ10") (pin "P$1") (pinfunction "1_P$1") (pintype "passive"))
      (node (ref "SJ12") (pin "1") (pinfunction "1_1") (pintype "passive"))
      (node (ref "SJ8") (pin "P$1") (pinfunction "1_P$1") (pintype "passive"))
      (node (ref "U12") (pin "9") (pinfunction "GND_9") (pintype "power_in"))
    )
    (net (code "100") (name "Net-(SJ11-1)") (class "Default")
      (node (ref "SJ11") (pin "P$1") (pinfunction "1_P$1") (pintype "passive"))
      (node (ref "SJ13") (pin "P$1") (pinfunction "1_P$1") (pintype "passive"))
      (node (ref "SJ9") (pin "P$1") (pinfunction "1_P$1") (pintype "passive"))
      (node (ref "U12") (pin "10") (pinfunction "CD+_10") (pintype "passive"))
      (node (ref "X8") (pin "9") (pinfunction "9_9") (pintype "passive"))
    )
    (net (code "101") (name "Net-(SJ15-1)") (class "Default")
      (node (ref "SJ15") (pin "P$1") (pinfunction "1_P$1") (pintype "passive"))
      (node (ref "SJ17") (pin "P$1") (pinfunction "1_P$1") (pintype "passive"))
      (node (ref "SJ19") (pin "1") (pinfunction "1_1") (pintype "passive"))
      (node (ref "U14") (pin "9") (pinfunction "GND_9") (pintype "power_in"))
    )
    (net (code "102") (name "Net-(SJ16-1)") (class "Default")
      (node (ref "SJ16") (pin "P$1") (pinfunction "1_P$1") (pintype "passive"))
      (node (ref "SJ18") (pin "P$1") (pinfunction "1_P$1") (pintype "passive"))
      (node (ref "SJ20") (pin "P$1") (pinfunction "1_P$1") (pintype "passive"))
      (node (ref "U14") (pin "10") (pinfunction "CD+_10") (pintype "passive"))
      (node (ref "X9") (pin "9") (pinfunction "9_9") (pintype "passive"))
    )
    (net (code "103") (name "Net-(U5A-O)") (class "Default")
      (node (ref "JP10") (pin "10") (pinfunction "10_10") (pintype "passive"))
      (node (ref "U5") (pin "7") (pinfunction "O_7") (pintype "output"))
      (node (ref "U6") (pin "7") (pinfunction "OUT_7") (pintype "output"))
      (node (ref "X7") (pin "1") (pinfunction "1_1") (pintype "passive"))
    )
    (net (code "104") (name "Net-(U5B-O)") (class "Default")
      (node (ref "JP10") (pin "9") (pinfunction "9_9") (pintype "passive"))
      (node (ref "U5") (pin "5") (pinfunction "O_5") (pintype "output"))
      (node (ref "U6") (pin "8") (pinfunction "OUT_8") (pintype "output"))
      (node (ref "X7") (pin "2") (pinfunction "2_2") (pintype "passive"))
    )
    (net (code "105") (name "Net-(U6A--IN)") (class "Default")
      (node (ref "R50") (pin "1") (pinfunction "1_1") (pintype "passive"))
      (node (ref "R51") (pin "2") (pinfunction "2_2") (pintype "passive"))
      (node (ref "U6") (pin "13") (pinfunction "-IN_13") (pintype "input"))
      (node (ref "U6") (pin "2") (pinfunction "-IN_2") (pintype "input"))
      (node (ref "U6") (pin "6") (pinfunction "-IN_6") (pintype "input"))
      (node (ref "U6") (pin "9") (pinfunction "-IN_9") (pintype "input"))
      (node (ref "U9") (pin "13") (pinfunction "-IN_13") (pintype "input"))
      (node (ref "U9") (pin "2") (pinfunction "-IN_2") (pintype "input"))
      (node (ref "U9") (pin "6") (pinfunction "-IN_6") (pintype "input"))
      (node (ref "U9") (pin "9") (pinfunction "-IN_9") (pintype "input"))
    )
    (net (code "106") (name "Net-(U6A-OUT)") (class "Default")
      (node (ref "JP10") (pin "8") (pinfunction "8_8") (pintype "passive"))
      (node (ref "U6") (pin "1") (pinfunction "OUT_1") (pintype "output"))
      (node (ref "U7") (pin "5") (pinfunction "O_5") (pintype "output"))
      (node (ref "X7") (pin "3") (pinfunction "3_3") (pintype "passive"))
    )
    (net (code "107") (name "Net-(U6D-OUT)") (class "Default")
      (node (ref "JP10") (pin "7") (pinfunction "7_7") (pintype "passive"))
      (node (ref "U6") (pin "14") (pinfunction "OUT_14") (pintype "output"))
      (node (ref "U7") (pin "7") (pinfunction "O_7") (pintype "output"))
      (node (ref "X7") (pin "4") (pinfunction "4_4") (pintype "passive"))
    )
    (net (code "108") (name "Net-(U8A-O)") (class "Default")
      (node (ref "JP10") (pin "4") (pinfunction "4_4") (pintype "passive"))
      (node (ref "U8") (pin "7") (pinfunction "O_7") (pintype "output"))
      (node (ref "U9") (pin "7") (pinfunction "OUT_7") (pintype "output"))
      (node (ref "X7") (pin "5") (pinfunction "5_5") (pintype "passive"))
    )
    (net (code "109") (name "Net-(U8B-O)") (class "Default")
      (node (ref "JP10") (pin "3") (pinfunction "3_3") (pintype "passive"))
      (node (ref "U8") (pin "5") (pinfunction "O_5") (pintype "output"))
      (node (ref "U9") (pin "8") (pinfunction "OUT_8") (pintype "output"))
      (node (ref "X7") (pin "6") (pinfunction "6_6") (pintype "passive"))
    )
    (net (code "110") (name "Net-(U10A-O)") (class "Default")
      (node (ref "JP10") (pin "1") (pinfunction "1_1") (pintype "passive"))
      (node (ref "U10") (pin "7") (pinfunction "O_7") (pintype "output"))
      (node (ref "U9") (pin "14") (pinfunction "OUT_14") (pintype "output"))
      (node (ref "X7") (pin "8") (pinfunction "8_8") (pintype "passive"))
    )
    (net (code "111") (name "Net-(U10B-O)") (class "Default")
      (node (ref "JP10") (pin "2") (pinfunction "2_2") (pintype "passive"))
      (node (ref "U10") (pin "5") (pinfunction "O_5") (pintype "output"))
      (node (ref "U9") (pin "1") (pinfunction "OUT_1") (pintype "output"))
      (node (ref "X7") (pin "7") (pinfunction "7_7") (pintype "passive"))
    )
    (net (code "112") (name "Net-(U11A-QA)") (class "Default")
      (node (ref "R59") (pin "1") (pinfunction "1_1") (pintype "passive"))
      (node (ref "U11") (pin "15") (pinfunction "QA_15") (pintype "tri_state"))
      (node (ref "U12") (pin "1") (pinfunction "I1_1") (pintype "input"))
    )
    (net (code "113") (name "Net-(U11A-QB)") (class "Default")
      (node (ref "R58") (pin "1") (pinfunction "1_1") (pintype "passive"))
      (node (ref "U11") (pin "1") (pinfunction "QB_1") (pintype "tri_state"))
      (node (ref "U12") (pin "2") (pinfunction "I2_2") (pintype "input"))
    )
    (net (code "114") (name "Net-(U11A-QC)") (class "Default")
      (node (ref "R57") (pin "1") (pinfunction "1_1") (pintype "passive"))
      (node (ref "U11") (pin "2") (pinfunction "QC_2") (pintype "tri_state"))
      (node (ref "U12") (pin "3") (pinfunction "I3_3") (pintype "input"))
    )
    (net (code "115") (name "Net-(U11A-QD)") (class "Default")
      (node (ref "R56") (pin "1") (pinfunction "1_1") (pintype "passive"))
      (node (ref "U11") (pin "3") (pinfunction "QD_3") (pintype "tri_state"))
      (node (ref "U12") (pin "4") (pinfunction "I4_4") (pintype "input"))
    )
    (net (code "116") (name "Net-(U11A-QE)") (class "Default")
      (node (ref "R55") (pin "1") (pinfunction "1_1") (pintype "passive"))
      (node (ref "U11") (pin "4") (pinfunction "QE_4") (pintype "tri_state"))
      (node (ref "U12") (pin "5") (pinfunction "I5_5") (pintype "input"))
    )
    (net (code "117") (name "Net-(U11A-QF)") (class "Default")
      (node (ref "R54") (pin "1") (pinfunction "1_1") (pintype "passive"))
      (node (ref "U11") (pin "5") (pinfunction "QF_5") (pintype "tri_state"))
      (node (ref "U12") (pin "6") (pinfunction "I6_6") (pintype "input"))
    )
    (net (code "118") (name "Net-(U11A-QG)") (class "Default")
      (node (ref "R53") (pin "1") (pinfunction "1_1") (pintype "passive"))
      (node (ref "U11") (pin "6") (pinfunction "QG_6") (pintype "tri_state"))
      (node (ref "U12") (pin "7") (pinfunction "I7_7") (pintype "input"))
    )
    (net (code "119") (name "Net-(U11A-QH)") (class "Default")
      (node (ref "R52") (pin "1") (pinfunction "1_1") (pintype "passive"))
      (node (ref "U11") (pin "7") (pinfunction "QH_7") (pintype "tri_state"))
      (node (ref "U12") (pin "8") (pinfunction "I8_8") (pintype "input"))
    )
    (net (code "120") (name "Net-(U13A-QA)") (class "Default")
      (node (ref "R67") (pin "1") (pinfunction "1_1") (pintype "passive"))
      (node (ref "U13") (pin "15") (pinfunction "QA_15") (pintype "tri_state"))
      (node (ref "U14") (pin "1") (pinfunction "I1_1") (pintype "input"))
    )
    (net (code "121") (name "Net-(U13A-QB)") (class "Default")
      (node (ref "R66") (pin "1") (pinfunction "1_1") (pintype "passive"))
      (node (ref "U13") (pin "1") (pinfunction "QB_1") (pintype "tri_state"))
      (node (ref "U14") (pin "2") (pinfunction "I2_2") (pintype "input"))
    )
    (net (code "122") (name "Net-(U13A-QC)") (class "Default")
      (node (ref "R65") (pin "1") (pinfunction "1_1") (pintype "passive"))
      (node (ref "U13") (pin "2") (pinfunction "QC_2") (pintype "tri_state"))
      (node (ref "U14") (pin "3") (pinfunction "I3_3") (pintype "input"))
    )
    (net (code "123") (name "Net-(U13A-QD)") (class "Default")
      (node (ref "R64") (pin "1") (pinfunction "1_1") (pintype "passive"))
      (node (ref "U13") (pin "3") (pinfunction "QD_3") (pintype "tri_state"))
      (node (ref "U14") (pin "4") (pinfunction "I4_4") (pintype "input"))
    )
    (net (code "124") (name "Net-(U13A-QE)") (class "Default")
      (node (ref "R63") (pin "1") (pinfunction "1_1") (pintype "passive"))
      (node (ref "U13") (pin "4") (pinfunction "QE_4") (pintype "tri_state"))
      (node (ref "U14") (pin "5") (pinfunction "I5_5") (pintype "input"))
    )
    (net (code "125") (name "Net-(U13A-QF)") (class "Default")
      (node (ref "R62") (pin "1") (pinfunction "1_1") (pintype "passive"))
      (node (ref "U13") (pin "5") (pinfunction "QF_5") (pintype "tri_state"))
      (node (ref "U14") (pin "6") (pinfunction "I6_6") (pintype "input"))
    )
    (net (code "126") (name "Net-(U13A-QG)") (class "Default")
      (node (ref "R61") (pin "1") (pinfunction "1_1") (pintype "passive"))
      (node (ref "U13") (pin "6") (pinfunction "QG_6") (pintype "tri_state"))
      (node (ref "U14") (pin "7") (pinfunction "I7_7") (pintype "input"))
    )
    (net (code "127") (name "Net-(U13A-QH)") (class "Default")
      (node (ref "R60") (pin "1") (pinfunction "1_1") (pintype "passive"))
      (node (ref "U13") (pin "7") (pinfunction "QH_7") (pintype "tri_state"))
      (node (ref "U14") (pin "8") (pinfunction "I8_8") (pintype "input"))
    )
    (net (code "128") (name "Net-(X1-Pad4)") (class "Default")
      (node (ref "X1") (pin "4") (pinfunction "4_4") (pintype "passive"))
      (node (ref "X2") (pin "4") (pinfunction "4_4") (pintype "passive"))
    )
    (net (code "129") (name "Net-(X1-Pad5)") (class "Default")
      (node (ref "X1") (pin "5") (pinfunction "5_5") (pintype "passive"))
      (node (ref "X2") (pin "5") (pinfunction "5_5") (pintype "passive"))
    )
    (net (code "130") (name "OLAT") (class "Default")
      (node (ref "G1") (pin "PA8") (pinfunction "PA8_PA8") (pintype "bidirectional"))
      (node (ref "R3") (pin "1") (pinfunction "1_1") (pintype "passive"))
      (node (ref "U11") (pin "12") (pinfunction "RCK_12") (pintype "input"))
      (node (ref "U13") (pin "12") (pinfunction "RCK_12") (pintype "input"))
    )
    (net (code "131") (name "SCK") (class "Default")
      (node (ref "G1") (pin "PB3") (pinfunction "PB3_PB3") (pintype "bidirectional"))
      (node (ref "JP5") (pin "3") (pinfunction "3_3") (pintype "passive"))
      (node (ref "R5") (pin "1") (pinfunction "1_1") (pintype "passive"))
      (node (ref "U11") (pin "11") (pinfunction "SCK_11") (pintype "input"))
      (node (ref "U13") (pin "11") (pinfunction "SCK_11") (pintype "input"))
    )
    (net (code "132") (name "SCK2") (class "Default")
      (node (ref "G1") (pin "PB10") (pinfunction "PB10_PB10") (pintype "bidirectional"))
      (node (ref "SJ2") (pin "P$1") (pinfunction "1_P$1") (pintype "passive"))
      (node (ref "U3") (pin "7") (pinfunction "CLK_7") (pintype "input"))
      (node (ref "U4") (pin "7") (pinfunction "CLK_7") (pintype "input"))
    )
    (net (code "133") (name "SLNK1") (class "Default")
      (node (ref "SJ14") (pin "P$1") (pinfunction "1_P$1") (pintype "passive"))
      (node (ref "U11") (pin "14") (pinfunction "SER_14") (pintype "input"))
      (node (ref "U13") (pin "9") (pinfunction "QH*_9") (pintype "tri_state"))
    )
    (net (code "134") (name "SLNK2") (class "Default")
      (node (ref "SJ5") (pin "P$1") (pinfunction "1_P$1") (pintype "passive"))
      (node (ref "U11") (pin "9") (pinfunction "QH*_9") (pintype "tri_state"))
    )
    (net (code "135") (name "SLNK3") (class "Default")
      (node (ref "SJ7") (pin "P$1") (pinfunction "1_P$1") (pintype "passive"))
      (node (ref "U3") (pin "1") (pinfunction "SER_1") (pintype "input"))
      (node (ref "U4") (pin "13") (pinfunction "QH_13") (pintype "output"))
    )
    (net (code "136") (name "SRV1") (class "Default")
      (node (ref "G1") (pin "PC9") (pinfunction "PC9_PC9") (pintype "bidirectional"))
      (node (ref "JP4") (pin "2") (pinfunction "2_2") (pintype "passive"))
      (node (ref "R13") (pin "2") (pinfunction "2_2") (pintype "passive"))
    )
    (net (code "137") (name "SRV2") (class "Default")
      (node (ref "G1") (pin "PC7") (pinfunction "PC7_PC7") (pintype "bidirectional"))
      (node (ref "JP4") (pin "1") (pinfunction "1_1") (pintype "passive"))
      (node (ref "R12") (pin "2") (pinfunction "2_2") (pintype "passive"))
    )
    (net (code "138") (name "SRV3") (class "Default")
      (node (ref "G1") (pin "PC8") (pinfunction "PC8_PC8") (pintype "bidirectional"))
      (node (ref "JP3") (pin "2") (pinfunction "2_2") (pintype "passive"))
      (node (ref "R11") (pin "2") (pinfunction "2_2") (pintype "passive"))
    )
    (net (code "139") (name "SRV4") (class "Default")
      (node (ref "G1") (pin "PC6") (pinfunction "PC6_PC6") (pintype "bidirectional"))
      (node (ref "JP3") (pin "1") (pinfunction "1_1") (pintype "passive"))
      (node (ref "R10") (pin "2") (pinfunction "2_2") (pintype "passive"))
    )
    (net (code "140") (name "SRV5") (class "Default")
      (node (ref "G1") (pin "PC12") (pinfunction "PC12_PC12") (pintype "bidirectional"))
      (node (ref "JP2") (pin "2") (pinfunction "2_2") (pintype "passive"))
      (node (ref "R9") (pin "2") (pinfunction "2_2") (pintype "passive"))
    )
    (net (code "141") (name "SRV6") (class "Default")
      (node (ref "G1") (pin "PA15") (pinfunction "PA15_PA15") (pintype "bidirectional"))
      (node (ref "JP2") (pin "1") (pinfunction "1_1") (pintype "passive"))
      (node (ref "R8") (pin "2") (pinfunction "2_2") (pintype "passive"))
    )
    (net (code "142") (name "SRV7") (class "Default")
      (node (ref "G1") (pin "PF1-PH1") (pinfunction "PF1-PH1_PF1-PH1") (pintype "bidirectional"))
      (node (ref "JP1") (pin "2") (pinfunction "2_2") (pintype "passive"))
      (node (ref "R7") (pin "2") (pinfunction "2_2") (pintype "passive"))
    )
    (net (code "143") (name "SRV8") (class "Default")
      (node (ref "G1") (pin "PD2") (pinfunction "PD2_PD2") (pintype "bidirectional"))
      (node (ref "JP1") (pin "1") (pinfunction "1_1") (pintype "passive"))
      (node (ref "R6") (pin "2") (pinfunction "2_2") (pintype "passive"))
    )
    (net (code "144") (name "TDRV1") (class "Default")
      (node (ref "G1") (pin "PB12") (pinfunction "PB12_PB12") (pintype "bidirectional"))
      (node (ref "U10") (pin "2") (pinfunction "I_2") (pintype "input"))
      (node (ref "U9") (pin "12") (pinfunction "+IN_12") (pintype "input"))
    )
    (net (code "145") (name "TDRV2") (class "Default")
      (node (ref "G1") (pin "PB2") (pinfunction "PB2_PB2") (pintype "bidirectional"))
      (node (ref "U10") (pin "4") (pinfunction "I_4") (pintype "input"))
      (node (ref "U9") (pin "3") (pinfunction "+IN_3") (pintype "input"))
    )
    (net (code "146") (name "TDRV3") (class "Default")
      (node (ref "G1") (pin "PB15") (pinfunction "PB15_PB15") (pintype "bidirectional"))
      (node (ref "U8") (pin "4") (pinfunction "I_4") (pintype "input"))
      (node (ref "U9") (pin "10") (pinfunction "+IN_10") (pintype "input"))
    )
    (net (code "147") (name "TDRV4") (class "Default")
      (node (ref "G1") (pin "PB1") (pinfunction "PB1_PB1") (pintype "bidirectional"))
      (node (ref "U8") (pin "2") (pinfunction "I_2") (pintype "input"))
      (node (ref "U9") (pin "5") (pinfunction "+IN_5") (pintype "input"))
    )
    (net (code "148") (name "TDRV5") (class "Default")
      (node (ref "G1") (pin "PA0") (pinfunction "PA0_PA0") (pintype "bidirectional"))
      (node (ref "U6") (pin "12") (pinfunction "+IN_12") (pintype "input"))
      (node (ref "U7") (pin "2") (pinfunction "I_2") (pintype "input"))
    )
    (net (code "149") (name "TDRV6") (class "Default")
      (node (ref "G1") (pin "PA4") (pinfunction "PA4_PA4") (pintype "bidirectional"))
      (node (ref "U6") (pin "3") (pinfunction "+IN_3") (pintype "input"))
      (node (ref "U7") (pin "4") (pinfunction "I_4") (pintype "input"))
    )
    (net (code "150") (name "TDRV7") (class "Default")
      (node (ref "G1") (pin "PC3") (pinfunction "PC3_PC3") (pintype "bidirectional"))
      (node (ref "U5") (pin "4") (pinfunction "I_4") (pintype "input"))
      (node (ref "U6") (pin "10") (pinfunction "+IN_10") (pintype "input"))
    )
    (net (code "151") (name "TDRV8") (class "Default")
      (node (ref "G1") (pin "PC0") (pinfunction "PC0_PC0") (pintype "bidirectional"))
      (node (ref "U5") (pin "2") (pinfunction "I_2") (pintype "input"))
      (node (ref "U6") (pin "5") (pinfunction "+IN_5") (pintype "input"))
    )
    (net (code "152") (name "V+") (class "Default")
      (node (ref "C6") (pin "+") (pinfunction "+_+") (pintype "passive"))
      (node (ref "C7") (pin "1") (pinfunction "1_1") (pintype "passive"))
      (node (ref "G1") (pin "E5V") (pinfunction "E5V_E5V") (pintype "power_in"))
      (node (ref "IC1") (pin "1") (pinfunction "FB_1") (pintype "input"))
      (node (ref "L1") (pin "1") (pinfunction "1_1") (pintype "passive"))
      (node (ref "U2") (pin "3") (pinfunction "FB_3") (pintype "bidirectional"))
    )
    (net (code "153") (name "unconnected-(G1-PadBOOT0)") (class "Default")
      (node (ref "G1") (pin "BOOT0") (pinfunction "BOOT0_BOOT0") (pintype "bidirectional"))
    )
    (net (code "154") (name "unconnected-(G1-PadIOREF2)") (class "Default")
      (node (ref "G1") (pin "IOREF2") (pinfunction "IOREF2_IOREF2") (pintype "input"))
    )
    (net (code "155") (name "unconnected-(G1-PadNC1-PF7)") (class "Default")
      (node (ref "G1") (pin "NC1-PF7") (pinfunction "NC1-PF7_NC1-PF7") (pintype "bidirectional"))
    )
    (net (code "156") (name "unconnected-(G1-PadNC2-PF6)") (class "Default")
      (node (ref "G1") (pin "NC2-PF6") (pinfunction "NC2-PF6_NC2-PF6") (pintype "bidirectional"))
    )
    (net (code "157") (name "unconnected-(G1-PadNC3)") (class "Default")
      (node (ref "G1") (pin "NC3") (pinfunction "NC3_NC3") (pintype "no_connect"))
    )
    (net (code "158") (name "unconnected-(G1-PadNC4)") (class "Default")
      (node (ref "G1") (pin "NC4") (pinfunction "NC4_NC4") (pintype "no_connect"))
    )
    (net (code "159") (name "unconnected-(G1-PadNC5-PD8)") (class "Default")
      (node (ref "G1") (pin "NC5-PD8") (pinfunction "NC5-PD8_NC5-PD8") (pintype "bidirectional"))
    )
    (net (code "160") (name "unconnected-(G1-PadNC6-PB11)") (class "Default")
      (node (ref "G1") (pin "NC6-PB11") (pinfunction "NC6-PB11_NC6-PB11") (pintype "no_connect"))
    )
    (net (code "161") (name "unconnected-(G1-PadNC7-PF5)") (class "Default")
      (node (ref "G1") (pin "NC7-PF5") (pinfunction "NC7-PF5_NC7-PF5") (pintype "bidirectional"))
    )
    (net (code "162") (name "unconnected-(G1-PadNC8-PF4)") (class "Default")
      (node (ref "G1") (pin "NC8-PF4") (pinfunction "NC8-PF4_NC8-PF4") (pintype "bidirectional"))
    )
    (net (code "163") (name "unconnected-(G1-PadNRESET)") (class "Default")
      (node (ref "G1") (pin "NRESET") (pinfunction "NRESET_NRESET") (pintype "input"))
    )
    (net (code "164") (name "unconnected-(G1-PadPA1)") (class "Default")
      (node (ref "G1") (pin "PA1") (pinfunction "PA1_PA1") (pintype "bidirectional"))
    )
    (net (code "165") (name "unconnected-(G1-PadPA2)") (class "Default")
      (node (ref "G1") (pin "PA2") (pinfunction "PA2_PA2") (pintype "bidirectional"))
    )
    (net (code "166") (name "unconnected-(G1-PadPA3)") (class "Default")
      (node (ref "G1") (pin "PA3") (pinfunction "PA3_PA3") (pintype "bidirectional"))
    )
    (net (code "167") (name "unconnected-(G1-PadPA5)") (class "Default")
      (node (ref "G1") (pin "PA5") (pinfunction "PA5_PA5") (pintype "bidirectional"))
    )
    (net (code "168") (name "unconnected-(G1-PadPA7)") (class "Default")
      (node (ref "G1") (pin "PA7") (pinfunction "PA7_PA7") (pintype "bidirectional"))
    )
    (net (code "169") (name "unconnected-(G1-PadPA9)") (class "Default")
      (node (ref "G1") (pin "PA9") (pinfunction "PA9_PA9") (pintype "bidirectional"))
    )
    (net (code "170") (name "unconnected-(G1-PadPA10)") (class "Default")
      (node (ref "G1") (pin "PA10") (pinfunction "PA10_PA10") (pintype "bidirectional"))
    )
    (net (code "171") (name "unconnected-(G1-PadPA11)") (class "Default")
      (node (ref "G1") (pin "PA11") (pinfunction "PA11_PA11") (pintype "bidirectional"))
    )
    (net (code "172") (name "unconnected-(G1-PadPA12)") (class "Default")
      (node (ref "G1") (pin "PA12") (pinfunction "PA12_PA12") (pintype "bidirectional"))
    )
    (net (code "173") (name "unconnected-(G1-PadPA13)") (class "Default")
      (node (ref "G1") (pin "PA13") (pinfunction "PA13_PA13") (pintype "bidirectional"))
    )
    (net (code "174") (name "unconnected-(G1-PadPA14)") (class "Default")
      (node (ref "G1") (pin "PA14") (pinfunction "PA14_PA14") (pintype "bidirectional"))
    )
    (net (code "175") (name "unconnected-(G1-PadPB0)") (class "Default")
      (node (ref "G1") (pin "PB0") (pinfunction "PB0_PB0") (pintype "bidirectional"))
    )
    (net (code "176") (name "unconnected-(G1-PadPC1)") (class "Default")
      (node (ref "G1") (pin "PC1") (pinfunction "PC1_PC1") (pintype "bidirectional"))
    )
    (net (code "177") (name "unconnected-(G1-PadPC4)") (class "Default")
      (node (ref "G1") (pin "PC4") (pinfunction "PC4_PC4") (pintype "bidirectional"))
    )
    (net (code "178") (name "unconnected-(G1-PadPC5)") (class "Default")
      (node (ref "G1") (pin "PC5") (pinfunction "PC5_PC5") (pintype "bidirectional"))
    )
    (net (code "179") (name "unconnected-(G1-PadPC13)") (class "Default")
      (node (ref "G1") (pin "PC13") (pinfunction "PC13_PC13") (pintype "bidirectional"))
    )
    (net (code "180") (name "unconnected-(G1-PadPC14)") (class "Default")
      (node (ref "G1") (pin "PC14") (pinfunction "PC14_PC14") (pintype "bidirectional"))
    )
    (net (code "181") (name "unconnected-(G1-PadPC15)") (class "Default")
      (node (ref "G1") (pin "PC15") (pinfunction "PC15_PC15") (pintype "bidirectional"))
    )
    (net (code "182") (name "unconnected-(G1-PadPF0-PH0)") (class "Default")
      (node (ref "G1") (pin "PF0-PH0") (pinfunction "PF0-PH0_PF0-PH0") (pintype "bidirectional"))
    )
    (net (code "183") (name "unconnected-(H1-MOUNT-PadB3,3)") (class "Default")
      (node (ref "H1") (pin "B3,3") (pinfunction "MOUNT_B3,3") (pintype "passive"))
    )
    (net (code "184") (name "unconnected-(H2-MOUNT-PadB3,3)") (class "Default")
      (node (ref "H2") (pin "B3,3") (pinfunction "MOUNT_B3,3") (pintype "passive"))
    )
    (net (code "185") (name "unconnected-(H3-MOUNT-PadB3,3)") (class "Default")
      (node (ref "H3") (pin "B3,3") (pinfunction "MOUNT_B3,3") (pintype "passive"))
    )
    (net (code "186") (name "unconnected-(H4-MOUNT-PadB3,3)") (class "Default")
      (node (ref "H4") (pin "B3,3") (pinfunction "MOUNT_B3,3") (pintype "passive"))
    )
  )
)
